# gpr-backplane-schematic-v1.net
KiCad netlist of a schematic drawn in EasyEDA
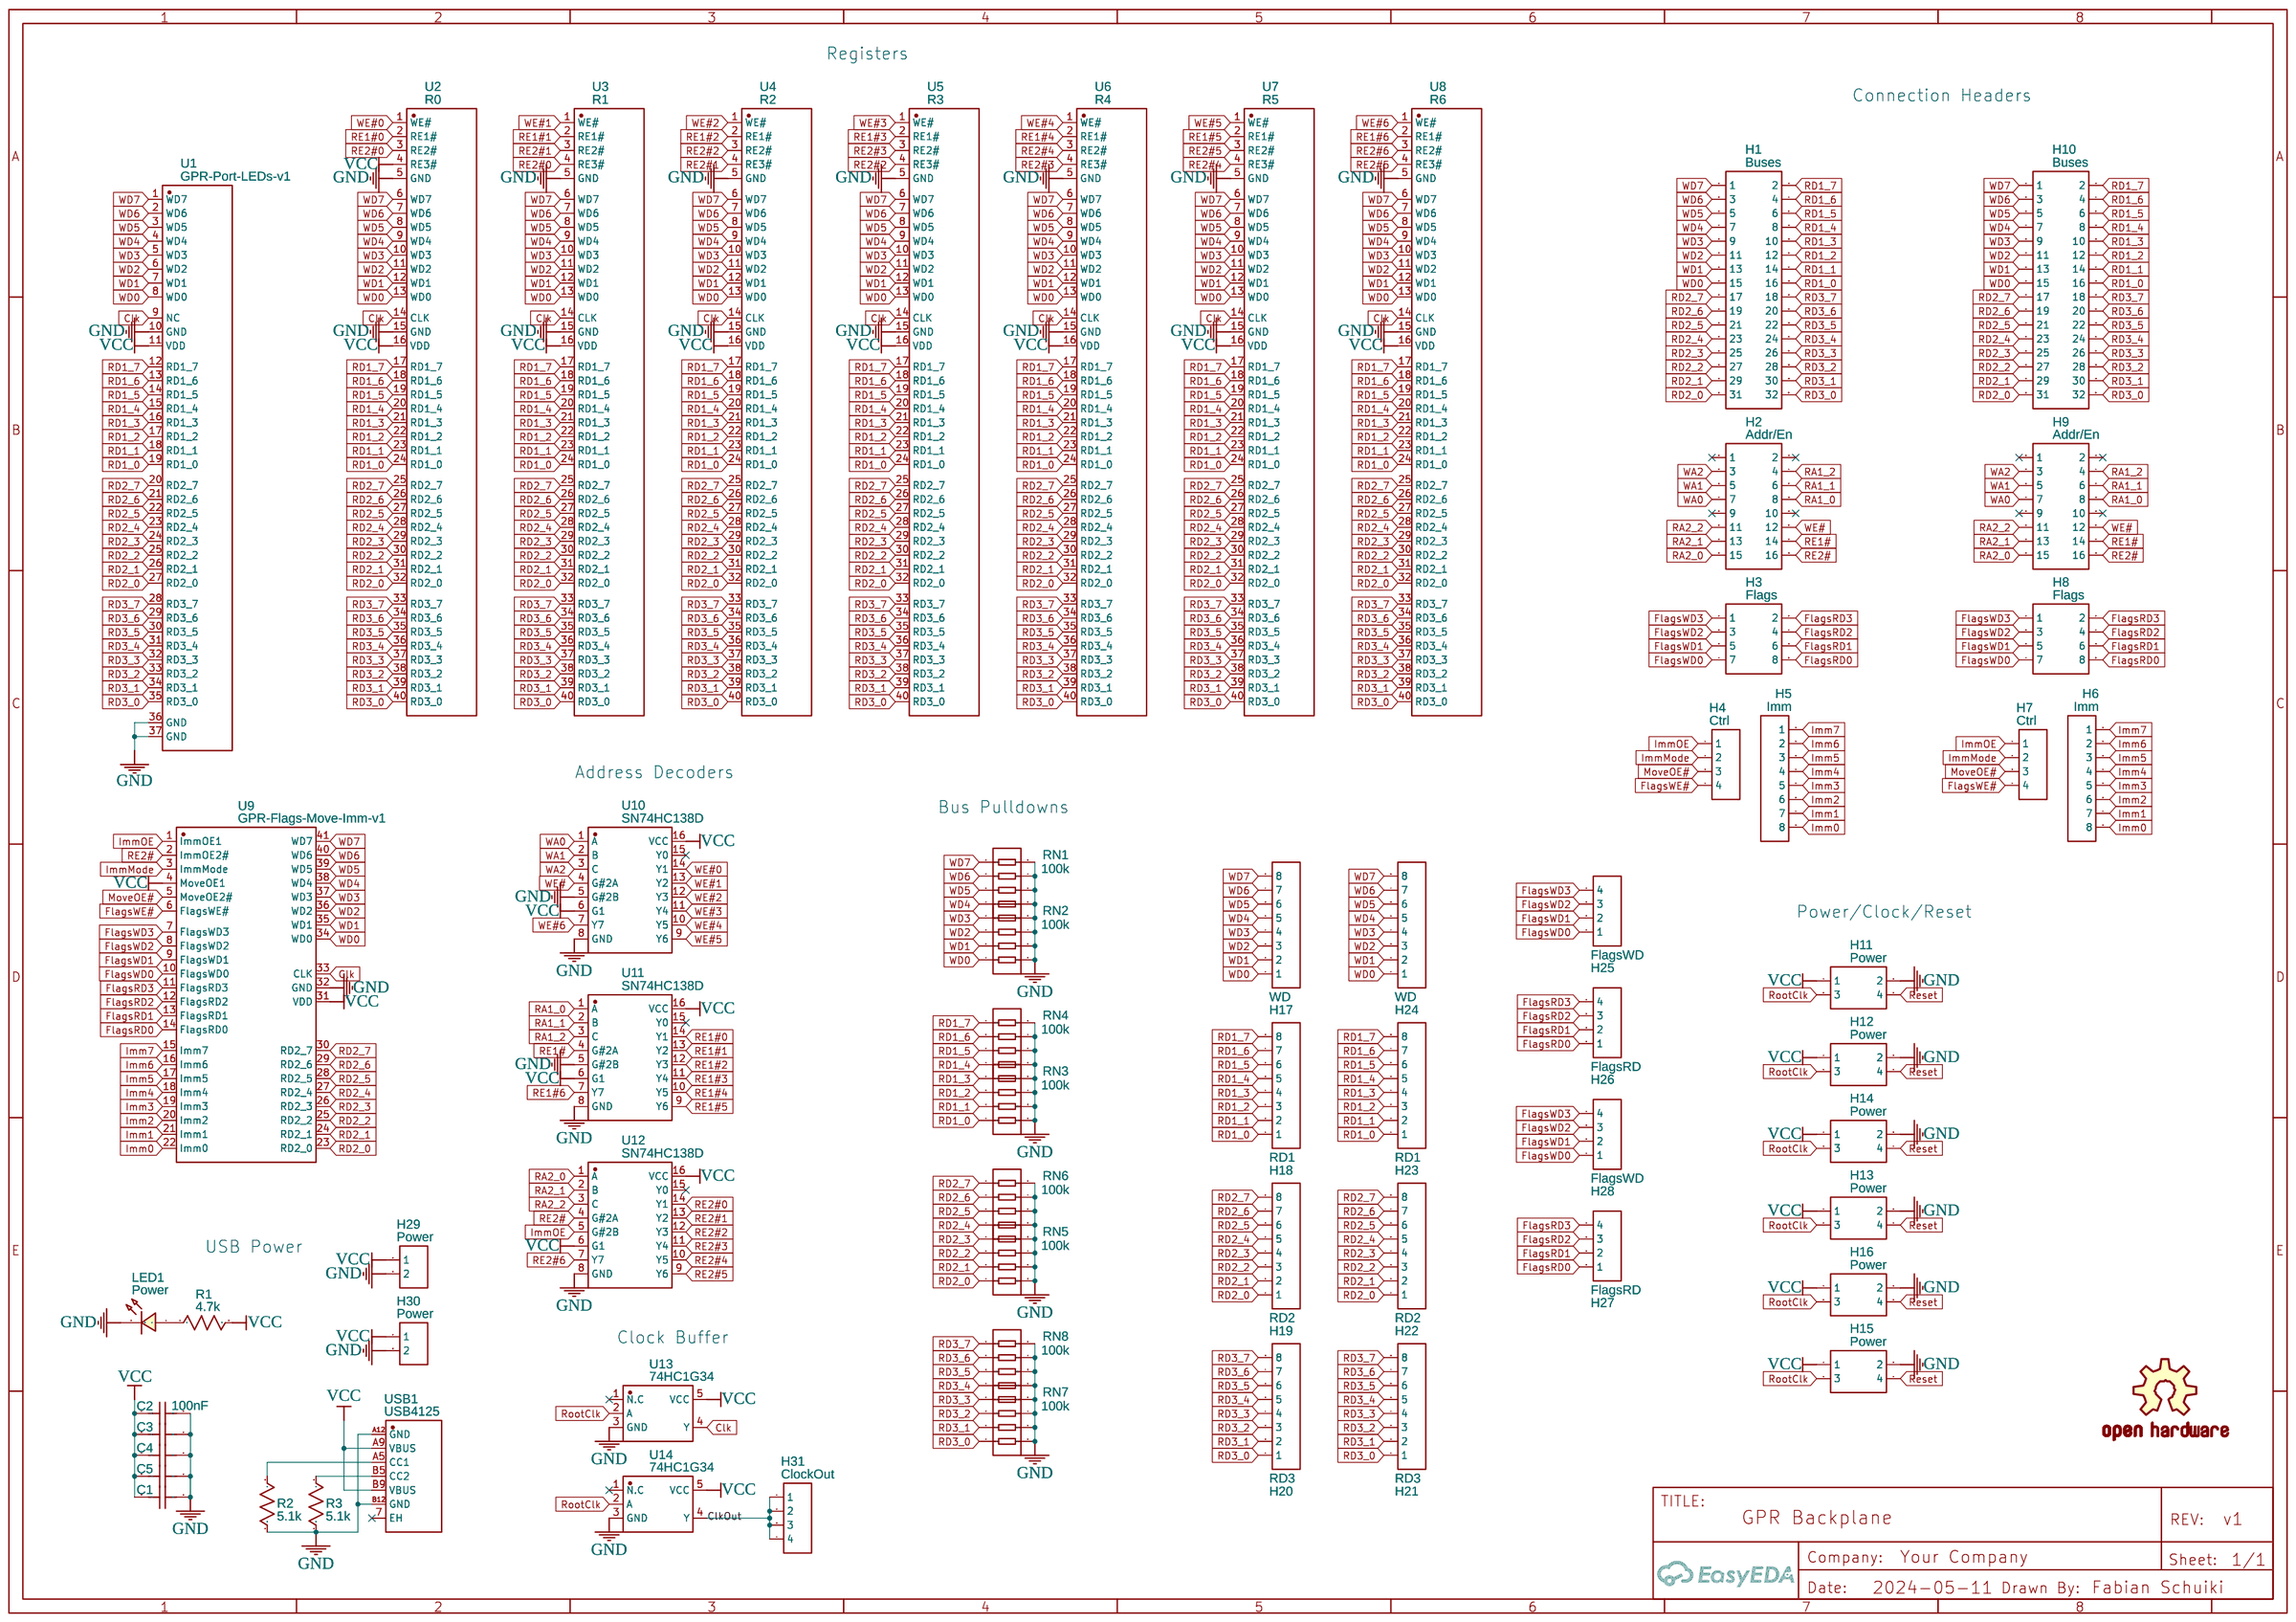
[diagram p0: schematic sheet]

(export (version "E")
  (design (tool "Eeschema 10.0.6"))
  (components
    (comp (ref "C1") (value "100nF") (libsource (lib "") (part "C_0603_US")))
    (comp (ref "C2") (value "100nF") (libsource (lib "") (part "C_0603_US")))
    (comp (ref "C3") (value "100nF") (libsource (lib "") (part "C_0603_US")))
    (comp (ref "C4") (value "100nF") (libsource (lib "") (part "C_0603_US")))
    (comp (ref "C5") (value "100nF") (libsource (lib "") (part "C_0603_US")))
    (comp (ref "H1")
      (value "Buses")
      (fields (field (name "BOM_Supplier Part") "C124382"))
      (libsource (lib "") (part "HDR-F-2.54_2x16"))
    )
    (comp (ref "H2")
      (value "Addr/En")
      (fields (field (name "BOM_Supplier Part") "C30734"))
      (libsource (lib "") (part "HDR-F-2.54_2x8"))
    )
    (comp (ref "H3")
      (value "Flags")
      (fields (field (name "BOM_Supplier Part") "C239344"))
      (libsource (lib "") (part "HDR-F-2.54_2x4"))
    )
    (comp (ref "H4")
      (value "Ctrl")
      (fields (field (name "BOM_Supplier Part") "C225501"))
      (libsource (lib "") (part "HDR-F-2.54_1x4_1"))
    )
    (comp (ref "H5")
      (value "Imm")
      (fields (field (name "BOM_Supplier Part") "C225505"))
      (libsource (lib "") (part "HDR-F-2.54_1x8_1"))
    )
    (comp (ref "H6")
      (value "Imm")
      (fields (field (name "BOM_Supplier Part") "C225505"))
      (libsource (lib "") (part "HDR-F-2.54_1x8_1"))
    )
    (comp (ref "H7")
      (value "Ctrl")
      (fields (field (name "BOM_Supplier Part") "C225501"))
      (libsource (lib "") (part "HDR-F-2.54_1x4_1"))
    )
    (comp (ref "H8")
      (value "Flags")
      (fields (field (name "BOM_Supplier Part") "C239344"))
      (libsource (lib "") (part "HDR-F-2.54_2x4"))
    )
    (comp (ref "H9")
      (value "Addr/En")
      (fields (field (name "BOM_Supplier Part") "C30734"))
      (libsource (lib "") (part "HDR-F-2.54_2x8"))
    )
    (comp (ref "H10")
      (value "Buses")
      (fields (field (name "BOM_Supplier Part") "C124382"))
      (libsource (lib "") (part "HDR-F-2.54_2x16"))
    )
    (comp (ref "H11")
      (value "Power")
      (fields (field (name "BOM_Supplier Part") "C239342"))
      (libsource (lib "") (part "HDR-F-2.54_2x2"))
    )
    (comp (ref "H12")
      (value "Power")
      (fields (field (name "BOM_Supplier Part") "C239342"))
      (libsource (lib "") (part "HDR-F-2.54_2x2"))
    )
    (comp (ref "H13")
      (value "Power")
      (fields (field (name "BOM_Supplier Part") "C239342"))
      (libsource (lib "") (part "HDR-F-2.54_2x2"))
    )
    (comp (ref "H14")
      (value "Power")
      (fields (field (name "BOM_Supplier Part") "C239342"))
      (libsource (lib "") (part "HDR-F-2.54_2x2"))
    )
    (comp (ref "H15")
      (value "Power")
      (fields (field (name "BOM_Supplier Part") "C239342"))
      (libsource (lib "") (part "HDR-F-2.54_2x2"))
    )
    (comp (ref "H16")
      (value "Power")
      (fields (field (name "BOM_Supplier Part") "C239342"))
      (libsource (lib "") (part "HDR-F-2.54_2x2"))
    )
    (comp (ref "H17")
      (value "WD")
      (fields (field (name "BOM_Supplier Part") "C225505"))
      (libsource (lib "") (part "HDR-F-2.54_1x8"))
    )
    (comp (ref "H18")
      (value "RD1")
      (fields (field (name "BOM_Supplier Part") "C225505"))
      (libsource (lib "") (part "HDR-F-2.54_1x8"))
    )
    (comp (ref "H19")
      (value "RD2")
      (fields (field (name "BOM_Supplier Part") "C225505"))
      (libsource (lib "") (part "HDR-F-2.54_1x8"))
    )
    (comp (ref "H20")
      (value "RD3")
      (fields (field (name "BOM_Supplier Part") "C225505"))
      (libsource (lib "") (part "HDR-F-2.54_1x8"))
    )
    (comp (ref "H21")
      (value "RD3")
      (fields (field (name "BOM_Supplier Part") "C225505"))
      (libsource (lib "") (part "HDR-F-2.54_1x8"))
    )
    (comp (ref "H22")
      (value "RD2")
      (fields (field (name "BOM_Supplier Part") "C225505"))
      (libsource (lib "") (part "HDR-F-2.54_1x8"))
    )
    (comp (ref "H23")
      (value "RD1")
      (fields (field (name "BOM_Supplier Part") "C225505"))
      (libsource (lib "") (part "HDR-F-2.54_1x8"))
    )
    (comp (ref "H24")
      (value "WD")
      (fields (field (name "BOM_Supplier Part") "C225505"))
      (libsource (lib "") (part "HDR-F-2.54_1x8"))
    )
    (comp (ref "H25")
      (value "FlagsWD")
      (fields (field (name "BOM_Supplier Part") "C225501"))
      (libsource (lib "") (part "HDR-F-2.54_1x4"))
    )
    (comp (ref "H26")
      (value "FlagsRD")
      (fields (field (name "BOM_Supplier Part") "C225501"))
      (libsource (lib "") (part "HDR-F-2.54_1x4"))
    )
    (comp (ref "H27")
      (value "FlagsRD")
      (fields (field (name "BOM_Supplier Part") "C225501"))
      (libsource (lib "") (part "HDR-F-2.54_1x4"))
    )
    (comp (ref "H28")
      (value "FlagsWD")
      (fields (field (name "BOM_Supplier Part") "C225501"))
      (libsource (lib "") (part "HDR-F-2.54_1x4"))
    )
    (comp (ref "H29")
      (value "Power")
      (fields (field (name "BOM_Supplier Part") "C49661"))
      (libsource (lib "") (part "HDR-F-2.54_1x2"))
    )
    (comp (ref "H30")
      (value "Power")
      (fields (field (name "BOM_Supplier Part") "C49661"))
      (libsource (lib "") (part "HDR-F-2.54_1x2"))
    )
    (comp (ref "H31")
      (value "ClockOut")
      (fields (field (name "BOM_Supplier Part") "C225501"))
      (libsource (lib "") (part "HDR-F-2.54_1x4_1"))
    )
    (comp (ref "LED1")
      (value "Power")
      (fields
        (field (name "BOM_Manufacturer Part") "D-B080508B1-KS2")
        (field (name "BOM_Supplier Part") "C108412")
      )
      (libsource (lib "") (part "LED-0805_B"))
    )
    (comp (ref "LOGO1") (value "ChannelLogo") (libsource (lib "") (part "ChannelLogo")))
    (comp (ref "LOGO2") (value "OSHW-LOGOL") (libsource (lib "") (part "OSHW-LOGOL")))
    (comp (ref "R1") (value "4.7k") (libsource (lib "") (part "R_0603_US_1")))
    (comp (ref "R2") (value "5.1k") (libsource (lib "") (part "R_0603_US")))
    (comp (ref "R3") (value "5.1k") (libsource (lib "") (part "R_0603_US")))
    (comp (ref "RN1")
      (value "100k")
      (fields
        (field (name "BOM_Manufacturer Part") "4D03WGJ0753T5E")
        (field (name "BOM_Supplier Part") "C425056")
      )
      (libsource (lib "") (part "4D03WGJ0753T5E"))
    )
    (comp (ref "RN2")
      (value "100k")
      (fields
        (field (name "BOM_Manufacturer Part") "4D03WGJ0753T5E")
        (field (name "BOM_Supplier Part") "C425056")
      )
      (libsource (lib "") (part "4D03WGJ0753T5E"))
    )
    (comp (ref "RN3")
      (value "100k")
      (fields
        (field (name "BOM_Manufacturer Part") "4D03WGJ0753T5E")
        (field (name "BOM_Supplier Part") "C425056")
      )
      (libsource (lib "") (part "4D03WGJ0753T5E"))
    )
    (comp (ref "RN4")
      (value "100k")
      (fields
        (field (name "BOM_Manufacturer Part") "4D03WGJ0753T5E")
        (field (name "BOM_Supplier Part") "C425056")
      )
      (libsource (lib "") (part "4D03WGJ0753T5E"))
    )
    (comp (ref "RN5")
      (value "100k")
      (fields
        (field (name "BOM_Manufacturer Part") "4D03WGJ0753T5E")
        (field (name "BOM_Supplier Part") "C425056")
      )
      (libsource (lib "") (part "4D03WGJ0753T5E"))
    )
    (comp (ref "RN6")
      (value "100k")
      (fields
        (field (name "BOM_Manufacturer Part") "4D03WGJ0753T5E")
        (field (name "BOM_Supplier Part") "C425056")
      )
      (libsource (lib "") (part "4D03WGJ0753T5E"))
    )
    (comp (ref "RN7")
      (value "100k")
      (fields
        (field (name "BOM_Manufacturer Part") "4D03WGJ0753T5E")
        (field (name "BOM_Supplier Part") "C425056")
      )
      (libsource (lib "") (part "4D03WGJ0753T5E"))
    )
    (comp (ref "RN8")
      (value "100k")
      (fields
        (field (name "BOM_Manufacturer Part") "4D03WGJ0753T5E")
        (field (name "BOM_Supplier Part") "C425056")
      )
      (libsource (lib "") (part "4D03WGJ0753T5E"))
    )
    (comp (ref "U1") (value "GPR-Port-LEDs-v1") (libsource (lib "") (part "GPR-Port-LEDs-v1")))
    (comp (ref "U2") (value "R0") (libsource (lib "") (part "GPR-v1")))
    (comp (ref "U3") (value "R1") (libsource (lib "") (part "GPR-v1")))
    (comp (ref "U4") (value "R2") (libsource (lib "") (part "GPR-v1")))
    (comp (ref "U5") (value "R3") (libsource (lib "") (part "GPR-v1")))
    (comp (ref "U6") (value "R4") (libsource (lib "") (part "GPR-v1")))
    (comp (ref "U7") (value "R5") (libsource (lib "") (part "GPR-v1")))
    (comp (ref "U8") (value "R6") (libsource (lib "") (part "GPR-v1")))
    (comp (ref "U9") (value "GPR-Flags-Move-Imm-v1") (libsource (lib "") (part "GPR-Flags-Move-Imm-v1")))
    (comp (ref "U10")
      (value "SN74HC138D")
      (fields (field (name "Manufacturer") "TI(德州仪器)"))
      (libsource (lib "") (part "SN74HC138D"))
    )
    (comp (ref "U11")
      (value "SN74HC138D")
      (fields (field (name "Manufacturer") "TI(德州仪器)"))
      (libsource (lib "") (part "SN74HC138D"))
    )
    (comp (ref "U12")
      (value "SN74HC138D")
      (fields (field (name "Manufacturer") "TI(德州仪器)"))
      (libsource (lib "") (part "SN74HC138D"))
    )
    (comp (ref "U13")
      (value "74HC1G34")
      (fields (field (name "Manufacturer Part") "SN74LVC1G34DBVRG4") (field (name "Manufacturer") "TI(德州仪器)"))
      (libsource (lib "") (part "SN74LVC1G34DBVRG4"))
    )
    (comp (ref "U14")
      (value "74HC1G34")
      (fields (field (name "Manufacturer Part") "SN74LVC1G34DBVRG4") (field (name "Manufacturer") "TI(德州仪器)"))
      (libsource (lib "") (part "SN74LVC1G34DBVRG4"))
    )
    (comp (ref "USB1")
      (value "USB4125")
      (fields
        (field (name "Manufacturer Part") "00401-UCAF001-X")
        (field (name "Manufacturer") "MINTRON(明硕)")
      )
      (libsource (lib "") (part "00401-UCAF001-X"))
    )
  )
  (nets
    (net (code "1") (name "/ClkOut") (class "Default")
      (node (ref "H31") (pin "1") (pinfunction "1_1") (pintype "unspecified"))
      (node (ref "H31") (pin "2") (pinfunction "2_2") (pintype "unspecified"))
      (node (ref "H31") (pin "3") (pinfunction "3_3") (pintype "unspecified"))
      (node (ref "H31") (pin "4") (pinfunction "4_4") (pintype "unspecified"))
      (node (ref "U14") (pin "4") (pinfunction "Y_4") (pintype "unspecified"))
    )
    (net (code "2") (name "Clk") (class "Default")
      (node (ref "U1") (pin "9") (pinfunction "NC_9") (pintype "unspecified"))
      (node (ref "U13") (pin "4") (pinfunction "Y_4") (pintype "unspecified"))
      (node (ref "U2") (pin "14") (pinfunction "CLK_14") (pintype "unspecified"))
      (node (ref "U3") (pin "14") (pinfunction "CLK_14") (pintype "unspecified"))
      (node (ref "U4") (pin "14") (pinfunction "CLK_14") (pintype "unspecified"))
      (node (ref "U5") (pin "14") (pinfunction "CLK_14") (pintype "unspecified"))
      (node (ref "U6") (pin "14") (pinfunction "CLK_14") (pintype "unspecified"))
      (node (ref "U7") (pin "14") (pinfunction "CLK_14") (pintype "unspecified"))
      (node (ref "U8") (pin "14") (pinfunction "CLK_14") (pintype "unspecified"))
      (node (ref "U9") (pin "33") (pinfunction "CLK_33") (pintype "unspecified"))
    )
    (net (code "3") (name "FlagsRD0") (class "Default")
      (node (ref "H26") (pin "1") (pinfunction "1_1") (pintype "unspecified"))
      (node (ref "H27") (pin "1") (pinfunction "1_1") (pintype "unspecified"))
      (node (ref "H3") (pin "8") (pinfunction "8_8") (pintype "unspecified"))
      (node (ref "H8") (pin "8") (pinfunction "8_8") (pintype "unspecified"))
      (node (ref "U9") (pin "14") (pinfunction "FlagsRD0_14") (pintype "unspecified"))
    )
    (net (code "4") (name "FlagsRD1") (class "Default")
      (node (ref "H26") (pin "2") (pinfunction "2_2") (pintype "unspecified"))
      (node (ref "H27") (pin "2") (pinfunction "2_2") (pintype "unspecified"))
      (node (ref "H3") (pin "6") (pinfunction "6_6") (pintype "unspecified"))
      (node (ref "H8") (pin "6") (pinfunction "6_6") (pintype "unspecified"))
      (node (ref "U9") (pin "13") (pinfunction "FlagsRD1_13") (pintype "unspecified"))
    )
    (net (code "5") (name "FlagsRD2") (class "Default")
      (node (ref "H26") (pin "3") (pinfunction "3_3") (pintype "unspecified"))
      (node (ref "H27") (pin "3") (pinfunction "3_3") (pintype "unspecified"))
      (node (ref "H3") (pin "4") (pinfunction "4_4") (pintype "unspecified"))
      (node (ref "H8") (pin "4") (pinfunction "4_4") (pintype "unspecified"))
      (node (ref "U9") (pin "12") (pinfunction "FlagsRD2_12") (pintype "unspecified"))
    )
    (net (code "6") (name "FlagsRD3") (class "Default")
      (node (ref "H26") (pin "4") (pinfunction "4_4") (pintype "unspecified"))
      (node (ref "H27") (pin "4") (pinfunction "4_4") (pintype "unspecified"))
      (node (ref "H3") (pin "2") (pinfunction "2_2") (pintype "unspecified"))
      (node (ref "H8") (pin "2") (pinfunction "2_2") (pintype "unspecified"))
      (node (ref "U9") (pin "11") (pinfunction "FlagsRD3_11") (pintype "unspecified"))
    )
    (net (code "7") (name "FlagsWD0") (class "Default")
      (node (ref "H25") (pin "1") (pinfunction "1_1") (pintype "unspecified"))
      (node (ref "H28") (pin "1") (pinfunction "1_1") (pintype "unspecified"))
      (node (ref "H3") (pin "7") (pinfunction "7_7") (pintype "unspecified"))
      (node (ref "H8") (pin "7") (pinfunction "7_7") (pintype "unspecified"))
      (node (ref "U9") (pin "10") (pinfunction "FlagsWD0_10") (pintype "unspecified"))
    )
    (net (code "8") (name "FlagsWD1") (class "Default")
      (node (ref "H25") (pin "2") (pinfunction "2_2") (pintype "unspecified"))
      (node (ref "H28") (pin "2") (pinfunction "2_2") (pintype "unspecified"))
      (node (ref "H3") (pin "5") (pinfunction "5_5") (pintype "unspecified"))
      (node (ref "H8") (pin "5") (pinfunction "5_5") (pintype "unspecified"))
      (node (ref "U9") (pin "9") (pinfunction "FlagsWD1_9") (pintype "unspecified"))
    )
    (net (code "9") (name "FlagsWD2") (class "Default")
      (node (ref "H25") (pin "3") (pinfunction "3_3") (pintype "unspecified"))
      (node (ref "H28") (pin "3") (pinfunction "3_3") (pintype "unspecified"))
      (node (ref "H3") (pin "3") (pinfunction "3_3") (pintype "unspecified"))
      (node (ref "H8") (pin "3") (pinfunction "3_3") (pintype "unspecified"))
      (node (ref "U9") (pin "8") (pinfunction "FlagsWD2_8") (pintype "unspecified"))
    )
    (net (code "10") (name "FlagsWD3") (class "Default")
      (node (ref "H25") (pin "4") (pinfunction "4_4") (pintype "unspecified"))
      (node (ref "H28") (pin "4") (pinfunction "4_4") (pintype "unspecified"))
      (node (ref "H3") (pin "1") (pinfunction "1_1") (pintype "unspecified"))
      (node (ref "H8") (pin "1") (pinfunction "1_1") (pintype "unspecified"))
      (node (ref "U9") (pin "7") (pinfunction "FlagsWD3_7") (pintype "unspecified"))
    )
    (net (code "11") (name "FlagsWE#") (class "Default")
      (node (ref "H4") (pin "4") (pinfunction "4_4") (pintype "unspecified"))
      (node (ref "H7") (pin "4") (pinfunction "4_4") (pintype "unspecified"))
      (node (ref "U9") (pin "6") (pinfunction "FlagsWE#_6") (pintype "unspecified"))
    )
    (net (code "12") (name "GND") (class "Default")
      (node (ref "C1") (pin "2") (pinfunction "2_2") (pintype "unspecified"))
      (node (ref "C2") (pin "2") (pinfunction "2_2") (pintype "unspecified"))
      (node (ref "C3") (pin "2") (pinfunction "2_2") (pintype "unspecified"))
      (node (ref "C4") (pin "2") (pinfunction "2_2") (pintype "unspecified"))
      (node (ref "C5") (pin "2") (pinfunction "2_2") (pintype "unspecified"))
      (node (ref "H11") (pin "2") (pinfunction "2_2") (pintype "unspecified"))
      (node (ref "H12") (pin "2") (pinfunction "2_2") (pintype "unspecified"))
      (node (ref "H13") (pin "2") (pinfunction "2_2") (pintype "unspecified"))
      (node (ref "H14") (pin "2") (pinfunction "2_2") (pintype "unspecified"))
      (node (ref "H15") (pin "2") (pinfunction "2_2") (pintype "unspecified"))
      (node (ref "H16") (pin "2") (pinfunction "2_2") (pintype "unspecified"))
      (node (ref "H29") (pin "2") (pinfunction "2_2") (pintype "input"))
      (node (ref "H30") (pin "2") (pinfunction "2_2") (pintype "input"))
      (node (ref "LED1") (pin "2") (pinfunction "2_2") (pintype "unspecified"))
      (node (ref "R2") (pin "1") (pinfunction "1_1") (pintype "unspecified"))
      (node (ref "R3") (pin "1") (pinfunction "1_1") (pintype "unspecified"))
      (node (ref "RN1") (pin "5") (pinfunction "5_5") (pintype "unspecified"))
      (node (ref "RN1") (pin "6") (pinfunction "6_6") (pintype "unspecified"))
      (node (ref "RN1") (pin "7") (pinfunction "7_7") (pintype "unspecified"))
      (node (ref "RN1") (pin "8") (pinfunction "8_8") (pintype "unspecified"))
      (node (ref "RN2") (pin "5") (pinfunction "5_5") (pintype "unspecified"))
      (node (ref "RN2") (pin "6") (pinfunction "6_6") (pintype "unspecified"))
      (node (ref "RN2") (pin "7") (pinfunction "7_7") (pintype "unspecified"))
      (node (ref "RN2") (pin "8") (pinfunction "8_8") (pintype "unspecified"))
      (node (ref "RN3") (pin "5") (pinfunction "5_5") (pintype "unspecified"))
      (node (ref "RN3") (pin "6") (pinfunction "6_6") (pintype "unspecified"))
      (node (ref "RN3") (pin "7") (pinfunction "7_7") (pintype "unspecified"))
      (node (ref "RN3") (pin "8") (pinfunction "8_8") (pintype "unspecified"))
      (node (ref "RN4") (pin "5") (pinfunction "5_5") (pintype "unspecified"))
      (node (ref "RN4") (pin "6") (pinfunction "6_6") (pintype "unspecified"))
      (node (ref "RN4") (pin "7") (pinfunction "7_7") (pintype "unspecified"))
      (node (ref "RN4") (pin "8") (pinfunction "8_8") (pintype "unspecified"))
      (node (ref "RN5") (pin "5") (pinfunction "5_5") (pintype "unspecified"))
      (node (ref "RN5") (pin "6") (pinfunction "6_6") (pintype "unspecified"))
      (node (ref "RN5") (pin "7") (pinfunction "7_7") (pintype "unspecified"))
      (node (ref "RN5") (pin "8") (pinfunction "8_8") (pintype "unspecified"))
      (node (ref "RN6") (pin "5") (pinfunction "5_5") (pintype "unspecified"))
      (node (ref "RN6") (pin "6") (pinfunction "6_6") (pintype "unspecified"))
      (node (ref "RN6") (pin "7") (pinfunction "7_7") (pintype "unspecified"))
      (node (ref "RN6") (pin "8") (pinfunction "8_8") (pintype "unspecified"))
      (node (ref "RN7") (pin "5") (pinfunction "5_5") (pintype "unspecified"))
      (node (ref "RN7") (pin "6") (pinfunction "6_6") (pintype "unspecified"))
      (node (ref "RN7") (pin "7") (pinfunction "7_7") (pintype "unspecified"))
      (node (ref "RN7") (pin "8") (pinfunction "8_8") (pintype "unspecified"))
      (node (ref "RN8") (pin "5") (pinfunction "5_5") (pintype "unspecified"))
      (node (ref "RN8") (pin "6") (pinfunction "6_6") (pintype "unspecified"))
      (node (ref "RN8") (pin "7") (pinfunction "7_7") (pintype "unspecified"))
      (node (ref "RN8") (pin "8") (pinfunction "8_8") (pintype "unspecified"))
      (node (ref "U1") (pin "10") (pinfunction "GND_10") (pintype "unspecified"))
      (node (ref "U1") (pin "36") (pinfunction "GND_36") (pintype "unspecified"))
      (node (ref "U1") (pin "37") (pinfunction "GND_37") (pintype "unspecified"))
      (node (ref "U10") (pin "5") (pinfunction "G#2B_5") (pintype "unspecified"))
      (node (ref "U10") (pin "8") (pinfunction "GND_8") (pintype "unspecified"))
      (node (ref "U11") (pin "5") (pinfunction "G#2B_5") (pintype "unspecified"))
      (node (ref "U11") (pin "8") (pinfunction "GND_8") (pintype "unspecified"))
      (node (ref "U12") (pin "8") (pinfunction "GND_8") (pintype "unspecified"))
      (node (ref "U13") (pin "3") (pinfunction "GND_3") (pintype "unspecified"))
      (node (ref "U14") (pin "3") (pinfunction "GND_3") (pintype "unspecified"))
      (node (ref "U2") (pin "15") (pinfunction "GND_15") (pintype "unspecified"))
      (node (ref "U2") (pin "5") (pinfunction "GND_5") (pintype "unspecified"))
      (node (ref "U3") (pin "15") (pinfunction "GND_15") (pintype "unspecified"))
      (node (ref "U3") (pin "5") (pinfunction "GND_5") (pintype "unspecified"))
      (node (ref "U4") (pin "15") (pinfunction "GND_15") (pintype "unspecified"))
      (node (ref "U4") (pin "5") (pinfunction "GND_5") (pintype "unspecified"))
      (node (ref "U5") (pin "15") (pinfunction "GND_15") (pintype "unspecified"))
      (node (ref "U5") (pin "5") (pinfunction "GND_5") (pintype "unspecified"))
      (node (ref "U6") (pin "15") (pinfunction "GND_15") (pintype "unspecified"))
      (node (ref "U6") (pin "5") (pinfunction "GND_5") (pintype "unspecified"))
      (node (ref "U7") (pin "15") (pinfunction "GND_15") (pintype "unspecified"))
      (node (ref "U7") (pin "5") (pinfunction "GND_5") (pintype "unspecified"))
      (node (ref "U8") (pin "15") (pinfunction "GND_15") (pintype "unspecified"))
      (node (ref "U8") (pin "5") (pinfunction "GND_5") (pintype "unspecified"))
      (node (ref "U9") (pin "32") (pinfunction "GND_32") (pintype "unspecified"))
      (node (ref "USB1") (pin "A12") (pinfunction "GND_A12") (pintype "unspecified"))
      (node (ref "USB1") (pin "B12") (pinfunction "GND_B12") (pintype "unspecified"))
    )
    (net (code "13") (name "Imm0") (class "Default")
      (node (ref "H5") (pin "8") (pinfunction "8_8") (pintype "unspecified"))
      (node (ref "H6") (pin "8") (pinfunction "8_8") (pintype "unspecified"))
      (node (ref "U9") (pin "22") (pinfunction "Imm0_22") (pintype "unspecified"))
    )
    (net (code "14") (name "Imm1") (class "Default")
      (node (ref "H5") (pin "7") (pinfunction "7_7") (pintype "unspecified"))
      (node (ref "H6") (pin "7") (pinfunction "7_7") (pintype "unspecified"))
      (node (ref "U9") (pin "21") (pinfunction "Imm1_21") (pintype "unspecified"))
    )
    (net (code "15") (name "Imm2") (class "Default")
      (node (ref "H5") (pin "6") (pinfunction "6_6") (pintype "unspecified"))
      (node (ref "H6") (pin "6") (pinfunction "6_6") (pintype "unspecified"))
      (node (ref "U9") (pin "20") (pinfunction "Imm2_20") (pintype "unspecified"))
    )
    (net (code "16") (name "Imm3") (class "Default")
      (node (ref "H5") (pin "5") (pinfunction "5_5") (pintype "unspecified"))
      (node (ref "H6") (pin "5") (pinfunction "5_5") (pintype "unspecified"))
      (node (ref "U9") (pin "19") (pinfunction "Imm3_19") (pintype "unspecified"))
    )
    (net (code "17") (name "Imm4") (class "Default")
      (node (ref "H5") (pin "4") (pinfunction "4_4") (pintype "unspecified"))
      (node (ref "H6") (pin "4") (pinfunction "4_4") (pintype "unspecified"))
      (node (ref "U9") (pin "18") (pinfunction "Imm4_18") (pintype "unspecified"))
    )
    (net (code "18") (name "Imm5") (class "Default")
      (node (ref "H5") (pin "3") (pinfunction "3_3") (pintype "unspecified"))
      (node (ref "H6") (pin "3") (pinfunction "3_3") (pintype "unspecified"))
      (node (ref "U9") (pin "17") (pinfunction "Imm5_17") (pintype "unspecified"))
    )
    (net (code "19") (name "Imm6") (class "Default")
      (node (ref "H5") (pin "2") (pinfunction "2_2") (pintype "unspecified"))
      (node (ref "H6") (pin "2") (pinfunction "2_2") (pintype "unspecified"))
      (node (ref "U9") (pin "16") (pinfunction "Imm6_16") (pintype "unspecified"))
    )
    (net (code "20") (name "Imm7") (class "Default")
      (node (ref "H5") (pin "1") (pinfunction "1_1") (pintype "unspecified"))
      (node (ref "H6") (pin "1") (pinfunction "1_1") (pintype "unspecified"))
      (node (ref "U9") (pin "15") (pinfunction "Imm7_15") (pintype "unspecified"))
    )
    (net (code "21") (name "ImmMode") (class "Default")
      (node (ref "H4") (pin "2") (pinfunction "2_2") (pintype "unspecified"))
      (node (ref "H7") (pin "2") (pinfunction "2_2") (pintype "unspecified"))
      (node (ref "U9") (pin "3") (pinfunction "ImmMode_3") (pintype "unspecified"))
    )
    (net (code "22") (name "ImmOE") (class "Default")
      (node (ref "H4") (pin "1") (pinfunction "1_1") (pintype "unspecified"))
      (node (ref "H7") (pin "1") (pinfunction "1_1") (pintype "unspecified"))
      (node (ref "U12") (pin "5") (pinfunction "G#2B_5") (pintype "unspecified"))
      (node (ref "U9") (pin "1") (pinfunction "ImmOE1_1") (pintype "unspecified"))
    )
    (net (code "23") (name "MoveOE#") (class "Default")
      (node (ref "H4") (pin "3") (pinfunction "3_3") (pintype "unspecified"))
      (node (ref "H7") (pin "3") (pinfunction "3_3") (pintype "unspecified"))
      (node (ref "U9") (pin "5") (pinfunction "MoveOE2#_5") (pintype "unspecified"))
    )
    (net (code "24") (name "Net-(LED1-Pad1)") (class "Default")
      (node (ref "LED1") (pin "1") (pinfunction "1_1") (pintype "unspecified"))
      (node (ref "R1") (pin "1") (pinfunction "1_1") (pintype "unspecified"))
    )
    (net (code "25") (name "Net-(USB1-CC1)") (class "Default")
      (node (ref "R2") (pin "2") (pinfunction "2_2") (pintype "unspecified"))
      (node (ref "USB1") (pin "A5") (pinfunction "CC1_A5") (pintype "unspecified"))
    )
    (net (code "26") (name "Net-(USB1-CC2)") (class "Default")
      (node (ref "R3") (pin "2") (pinfunction "2_2") (pintype "unspecified"))
      (node (ref "USB1") (pin "B5") (pinfunction "CC2_B5") (pintype "unspecified"))
    )
    (net (code "27") (name "RA1_0") (class "Default")
      (node (ref "H2") (pin "8") (pinfunction "8_8") (pintype "input"))
      (node (ref "H9") (pin "8") (pinfunction "8_8") (pintype "input"))
      (node (ref "U11") (pin "1") (pinfunction "A_1") (pintype "unspecified"))
    )
    (net (code "28") (name "RA1_1") (class "Default")
      (node (ref "H2") (pin "6") (pinfunction "6_6") (pintype "input"))
      (node (ref "H9") (pin "6") (pinfunction "6_6") (pintype "input"))
      (node (ref "U11") (pin "2") (pinfunction "B_2") (pintype "unspecified"))
    )
    (net (code "29") (name "RA1_2") (class "Default")
      (node (ref "H2") (pin "4") (pinfunction "4_4") (pintype "input"))
      (node (ref "H9") (pin "4") (pinfunction "4_4") (pintype "input"))
      (node (ref "U11") (pin "3") (pinfunction "C_3") (pintype "unspecified"))
    )
    (net (code "30") (name "RA2_0") (class "Default")
      (node (ref "H2") (pin "15") (pinfunction "15_15") (pintype "input"))
      (node (ref "H9") (pin "15") (pinfunction "15_15") (pintype "input"))
      (node (ref "U12") (pin "1") (pinfunction "A_1") (pintype "unspecified"))
    )
    (net (code "31") (name "RA2_1") (class "Default")
      (node (ref "H2") (pin "13") (pinfunction "13_13") (pintype "input"))
      (node (ref "H9") (pin "13") (pinfunction "13_13") (pintype "input"))
      (node (ref "U12") (pin "2") (pinfunction "B_2") (pintype "unspecified"))
    )
    (net (code "32") (name "RA2_2") (class "Default")
      (node (ref "H2") (pin "11") (pinfunction "11_11") (pintype "input"))
      (node (ref "H9") (pin "11") (pinfunction "11_11") (pintype "input"))
      (node (ref "U12") (pin "3") (pinfunction "C_3") (pintype "unspecified"))
    )
    (net (code "33") (name "RD1_0") (class "Default")
      (node (ref "H1") (pin "16") (pinfunction "16_16") (pintype "input"))
      (node (ref "H10") (pin "16") (pinfunction "16_16") (pintype "input"))
      (node (ref "H18") (pin "1") (pinfunction "1_1") (pintype "unspecified"))
      (node (ref "H23") (pin "1") (pinfunction "1_1") (pintype "unspecified"))
      (node (ref "RN3") (pin "4") (pinfunction "4_4") (pintype "unspecified"))
      (node (ref "U1") (pin "19") (pinfunction "RD1_0_19") (pintype "unspecified"))
      (node (ref "U2") (pin "24") (pinfunction "RD1_0_24") (pintype "unspecified"))
      (node (ref "U3") (pin "24") (pinfunction "RD1_0_24") (pintype "unspecified"))
      (node (ref "U4") (pin "24") (pinfunction "RD1_0_24") (pintype "unspecified"))
      (node (ref "U5") (pin "24") (pinfunction "RD1_0_24") (pintype "unspecified"))
      (node (ref "U6") (pin "24") (pinfunction "RD1_0_24") (pintype "unspecified"))
      (node (ref "U7") (pin "24") (pinfunction "RD1_0_24") (pintype "unspecified"))
      (node (ref "U8") (pin "24") (pinfunction "RD1_0_24") (pintype "unspecified"))
    )
    (net (code "34") (name "RD1_1") (class "Default")
      (node (ref "H1") (pin "14") (pinfunction "14_14") (pintype "input"))
      (node (ref "H10") (pin "14") (pinfunction "14_14") (pintype "input"))
      (node (ref "H18") (pin "2") (pinfunction "2_2") (pintype "unspecified"))
      (node (ref "H23") (pin "2") (pinfunction "2_2") (pintype "unspecified"))
      (node (ref "RN3") (pin "3") (pinfunction "3_3") (pintype "unspecified"))
      (node (ref "U1") (pin "18") (pinfunction "RD1_1_18") (pintype "unspecified"))
      (node (ref "U2") (pin "23") (pinfunction "RD1_1_23") (pintype "unspecified"))
      (node (ref "U3") (pin "23") (pinfunction "RD1_1_23") (pintype "unspecified"))
      (node (ref "U4") (pin "23") (pinfunction "RD1_1_23") (pintype "unspecified"))
      (node (ref "U5") (pin "23") (pinfunction "RD1_1_23") (pintype "unspecified"))
      (node (ref "U6") (pin "23") (pinfunction "RD1_1_23") (pintype "unspecified"))
      (node (ref "U7") (pin "23") (pinfunction "RD1_1_23") (pintype "unspecified"))
      (node (ref "U8") (pin "23") (pinfunction "RD1_1_23") (pintype "unspecified"))
    )
    (net (code "35") (name "RD1_2") (class "Default")
      (node (ref "H1") (pin "12") (pinfunction "12_12") (pintype "input"))
      (node (ref "H10") (pin "12") (pinfunction "12_12") (pintype "input"))
      (node (ref "H18") (pin "3") (pinfunction "3_3") (pintype "unspecified"))
      (node (ref "H23") (pin "3") (pinfunction "3_3") (pintype "unspecified"))
      (node (ref "RN3") (pin "2") (pinfunction "2_2") (pintype "unspecified"))
      (node (ref "U1") (pin "17") (pinfunction "RD1_2_17") (pintype "unspecified"))
      (node (ref "U2") (pin "22") (pinfunction "RD1_2_22") (pintype "unspecified"))
      (node (ref "U3") (pin "22") (pinfunction "RD1_2_22") (pintype "unspecified"))
      (node (ref "U4") (pin "22") (pinfunction "RD1_2_22") (pintype "unspecified"))
      (node (ref "U5") (pin "22") (pinfunction "RD1_2_22") (pintype "unspecified"))
      (node (ref "U6") (pin "22") (pinfunction "RD1_2_22") (pintype "unspecified"))
      (node (ref "U7") (pin "22") (pinfunction "RD1_2_22") (pintype "unspecified"))
      (node (ref "U8") (pin "22") (pinfunction "RD1_2_22") (pintype "unspecified"))
    )
    (net (code "36") (name "RD1_3") (class "Default")
      (node (ref "H1") (pin "10") (pinfunction "10_10") (pintype "input"))
      (node (ref "H10") (pin "10") (pinfunction "10_10") (pintype "input"))
      (node (ref "H18") (pin "4") (pinfunction "4_4") (pintype "unspecified"))
      (node (ref "H23") (pin "4") (pinfunction "4_4") (pintype "unspecified"))
      (node (ref "RN3") (pin "1") (pinfunction "1_1") (pintype "unspecified"))
      (node (ref "U1") (pin "16") (pinfunction "RD1_3_16") (pintype "unspecified"))
      (node (ref "U2") (pin "21") (pinfunction "RD1_3_21") (pintype "unspecified"))
      (node (ref "U3") (pin "21") (pinfunction "RD1_3_21") (pintype "unspecified"))
      (node (ref "U4") (pin "21") (pinfunction "RD1_3_21") (pintype "unspecified"))
      (node (ref "U5") (pin "21") (pinfunction "RD1_3_21") (pintype "unspecified"))
      (node (ref "U6") (pin "21") (pinfunction "RD1_3_21") (pintype "unspecified"))
      (node (ref "U7") (pin "21") (pinfunction "RD1_3_21") (pintype "unspecified"))
      (node (ref "U8") (pin "21") (pinfunction "RD1_3_21") (pintype "unspecified"))
    )
    (net (code "37") (name "RD1_4") (class "Default")
      (node (ref "H1") (pin "8") (pinfunction "8_8") (pintype "input"))
      (node (ref "H10") (pin "8") (pinfunction "8_8") (pintype "input"))
      (node (ref "H18") (pin "5") (pinfunction "5_5") (pintype "unspecified"))
      (node (ref "H23") (pin "5") (pinfunction "5_5") (pintype "unspecified"))
      (node (ref "RN4") (pin "4") (pinfunction "4_4") (pintype "unspecified"))
      (node (ref "U1") (pin "15") (pinfunction "RD1_4_15") (pintype "unspecified"))
      (node (ref "U2") (pin "20") (pinfunction "RD1_4_20") (pintype "unspecified"))
      (node (ref "U3") (pin "20") (pinfunction "RD1_4_20") (pintype "unspecified"))
      (node (ref "U4") (pin "20") (pinfunction "RD1_4_20") (pintype "unspecified"))
      (node (ref "U5") (pin "20") (pinfunction "RD1_4_20") (pintype "unspecified"))
      (node (ref "U6") (pin "20") (pinfunction "RD1_4_20") (pintype "unspecified"))
      (node (ref "U7") (pin "20") (pinfunction "RD1_4_20") (pintype "unspecified"))
      (node (ref "U8") (pin "20") (pinfunction "RD1_4_20") (pintype "unspecified"))
    )
    (net (code "38") (name "RD1_5") (class "Default")
      (node (ref "H1") (pin "6") (pinfunction "6_6") (pintype "input"))
      (node (ref "H10") (pin "6") (pinfunction "6_6") (pintype "input"))
      (node (ref "H18") (pin "6") (pinfunction "6_6") (pintype "unspecified"))
      (node (ref "H23") (pin "6") (pinfunction "6_6") (pintype "unspecified"))
      (node (ref "RN4") (pin "3") (pinfunction "3_3") (pintype "unspecified"))
      (node (ref "U1") (pin "14") (pinfunction "RD1_5_14") (pintype "unspecified"))
      (node (ref "U2") (pin "19") (pinfunction "RD1_5_19") (pintype "unspecified"))
      (node (ref "U3") (pin "19") (pinfunction "RD1_5_19") (pintype "unspecified"))
      (node (ref "U4") (pin "19") (pinfunction "RD1_5_19") (pintype "unspecified"))
      (node (ref "U5") (pin "19") (pinfunction "RD1_5_19") (pintype "unspecified"))
      (node (ref "U6") (pin "19") (pinfunction "RD1_5_19") (pintype "unspecified"))
      (node (ref "U7") (pin "19") (pinfunction "RD1_5_19") (pintype "unspecified"))
      (node (ref "U8") (pin "19") (pinfunction "RD1_5_19") (pintype "unspecified"))
    )
    (net (code "39") (name "RD1_6") (class "Default")
      (node (ref "H1") (pin "4") (pinfunction "4_4") (pintype "input"))
      (node (ref "H10") (pin "4") (pinfunction "4_4") (pintype "input"))
      (node (ref "H18") (pin "7") (pinfunction "7_7") (pintype "unspecified"))
      (node (ref "H23") (pin "7") (pinfunction "7_7") (pintype "unspecified"))
      (node (ref "RN4") (pin "2") (pinfunction "2_2") (pintype "unspecified"))
      (node (ref "U1") (pin "13") (pinfunction "RD1_6_13") (pintype "unspecified"))
      (node (ref "U2") (pin "18") (pinfunction "RD1_6_18") (pintype "unspecified"))
      (node (ref "U3") (pin "18") (pinfunction "RD1_6_18") (pintype "unspecified"))
      (node (ref "U4") (pin "18") (pinfunction "RD1_6_18") (pintype "unspecified"))
      (node (ref "U5") (pin "18") (pinfunction "RD1_6_18") (pintype "unspecified"))
      (node (ref "U6") (pin "18") (pinfunction "RD1_6_18") (pintype "unspecified"))
      (node (ref "U7") (pin "18") (pinfunction "RD1_6_18") (pintype "unspecified"))
      (node (ref "U8") (pin "18") (pinfunction "RD1_6_18") (pintype "unspecified"))
    )
    (net (code "40") (name "RD1_7") (class "Default")
      (node (ref "H1") (pin "2") (pinfunction "2_2") (pintype "input"))
      (node (ref "H10") (pin "2") (pinfunction "2_2") (pintype "input"))
      (node (ref "H18") (pin "8") (pinfunction "8_8") (pintype "unspecified"))
      (node (ref "H23") (pin "8") (pinfunction "8_8") (pintype "unspecified"))
      (node (ref "RN4") (pin "1") (pinfunction "1_1") (pintype "unspecified"))
      (node (ref "U1") (pin "12") (pinfunction "RD1_7_12") (pintype "unspecified"))
      (node (ref "U2") (pin "17") (pinfunction "RD1_7_17") (pintype "unspecified"))
      (node (ref "U3") (pin "17") (pinfunction "RD1_7_17") (pintype "unspecified"))
      (node (ref "U4") (pin "17") (pinfunction "RD1_7_17") (pintype "unspecified"))
      (node (ref "U5") (pin "17") (pinfunction "RD1_7_17") (pintype "unspecified"))
      (node (ref "U6") (pin "17") (pinfunction "RD1_7_17") (pintype "unspecified"))
      (node (ref "U7") (pin "17") (pinfunction "RD1_7_17") (pintype "unspecified"))
      (node (ref "U8") (pin "17") (pinfunction "RD1_7_17") (pintype "unspecified"))
    )
    (net (code "41") (name "RD2_0") (class "Default")
      (node (ref "H1") (pin "31") (pinfunction "31_31") (pintype "input"))
      (node (ref "H10") (pin "31") (pinfunction "31_31") (pintype "input"))
      (node (ref "H19") (pin "1") (pinfunction "1_1") (pintype "unspecified"))
      (node (ref "H22") (pin "1") (pinfunction "1_1") (pintype "unspecified"))
      (node (ref "RN5") (pin "4") (pinfunction "4_4") (pintype "unspecified"))
      (node (ref "U1") (pin "27") (pinfunction "RD2_0_27") (pintype "unspecified"))
      (node (ref "U2") (pin "32") (pinfunction "RD2_0_32") (pintype "unspecified"))
      (node (ref "U3") (pin "32") (pinfunction "RD2_0_32") (pintype "unspecified"))
      (node (ref "U4") (pin "32") (pinfunction "RD2_0_32") (pintype "unspecified"))
      (node (ref "U5") (pin "32") (pinfunction "RD2_0_32") (pintype "unspecified"))
      (node (ref "U6") (pin "32") (pinfunction "RD2_0_32") (pintype "unspecified"))
      (node (ref "U7") (pin "32") (pinfunction "RD2_0_32") (pintype "unspecified"))
      (node (ref "U8") (pin "32") (pinfunction "RD2_0_32") (pintype "unspecified"))
      (node (ref "U9") (pin "23") (pinfunction "RD2_0_23") (pintype "unspecified"))
    )
    (net (code "42") (name "RD2_1") (class "Default")
      (node (ref "H1") (pin "29") (pinfunction "29_29") (pintype "input"))
      (node (ref "H10") (pin "29") (pinfunction "29_29") (pintype "input"))
      (node (ref "H19") (pin "2") (pinfunction "2_2") (pintype "unspecified"))
      (node (ref "H22") (pin "2") (pinfunction "2_2") (pintype "unspecified"))
      (node (ref "RN5") (pin "3") (pinfunction "3_3") (pintype "unspecified"))
      (node (ref "U1") (pin "26") (pinfunction "RD2_1_26") (pintype "unspecified"))
      (node (ref "U2") (pin "31") (pinfunction "RD2_1_31") (pintype "unspecified"))
      (node (ref "U3") (pin "31") (pinfunction "RD2_1_31") (pintype "unspecified"))
      (node (ref "U4") (pin "31") (pinfunction "RD2_1_31") (pintype "unspecified"))
      (node (ref "U5") (pin "31") (pinfunction "RD2_1_31") (pintype "unspecified"))
      (node (ref "U6") (pin "31") (pinfunction "RD2_1_31") (pintype "unspecified"))
      (node (ref "U7") (pin "31") (pinfunction "RD2_1_31") (pintype "unspecified"))
      (node (ref "U8") (pin "31") (pinfunction "RD2_1_31") (pintype "unspecified"))
      (node (ref "U9") (pin "24") (pinfunction "RD2_1_24") (pintype "unspecified"))
    )
    (net (code "43") (name "RD2_2") (class "Default")
      (node (ref "H1") (pin "27") (pinfunction "27_27") (pintype "input"))
      (node (ref "H10") (pin "27") (pinfunction "27_27") (pintype "input"))
      (node (ref "H19") (pin "3") (pinfunction "3_3") (pintype "unspecified"))
      (node (ref "H22") (pin "3") (pinfunction "3_3") (pintype "unspecified"))
      (node (ref "RN5") (pin "2") (pinfunction "2_2") (pintype "unspecified"))
      (node (ref "U1") (pin "25") (pinfunction "RD2_2_25") (pintype "unspecified"))
      (node (ref "U2") (pin "30") (pinfunction "RD2_2_30") (pintype "unspecified"))
      (node (ref "U3") (pin "30") (pinfunction "RD2_2_30") (pintype "unspecified"))
      (node (ref "U4") (pin "30") (pinfunction "RD2_2_30") (pintype "unspecified"))
      (node (ref "U5") (pin "30") (pinfunction "RD2_2_30") (pintype "unspecified"))
      (node (ref "U6") (pin "30") (pinfunction "RD2_2_30") (pintype "unspecified"))
      (node (ref "U7") (pin "30") (pinfunction "RD2_2_30") (pintype "unspecified"))
      (node (ref "U8") (pin "30") (pinfunction "RD2_2_30") (pintype "unspecified"))
      (node (ref "U9") (pin "25") (pinfunction "RD2_2_25") (pintype "unspecified"))
    )
    (net (code "44") (name "RD2_3") (class "Default")
      (node (ref "H1") (pin "25") (pinfunction "25_25") (pintype "input"))
      (node (ref "H10") (pin "25") (pinfunction "25_25") (pintype "input"))
      (node (ref "H19") (pin "4") (pinfunction "4_4") (pintype "unspecified"))
      (node (ref "H22") (pin "4") (pinfunction "4_4") (pintype "unspecified"))
      (node (ref "RN5") (pin "1") (pinfunction "1_1") (pintype "unspecified"))
      (node (ref "U1") (pin "24") (pinfunction "RD2_3_24") (pintype "unspecified"))
      (node (ref "U2") (pin "29") (pinfunction "RD2_3_29") (pintype "unspecified"))
      (node (ref "U3") (pin "29") (pinfunction "RD2_3_29") (pintype "unspecified"))
      (node (ref "U4") (pin "29") (pinfunction "RD2_3_29") (pintype "unspecified"))
      (node (ref "U5") (pin "29") (pinfunction "RD2_3_29") (pintype "unspecified"))
      (node (ref "U6") (pin "29") (pinfunction "RD2_3_29") (pintype "unspecified"))
      (node (ref "U7") (pin "29") (pinfunction "RD2_3_29") (pintype "unspecified"))
      (node (ref "U8") (pin "29") (pinfunction "RD2_3_29") (pintype "unspecified"))
      (node (ref "U9") (pin "26") (pinfunction "RD2_3_26") (pintype "unspecified"))
    )
    (net (code "45") (name "RD2_4") (class "Default")
      (node (ref "H1") (pin "23") (pinfunction "23_23") (pintype "input"))
      (node (ref "H10") (pin "23") (pinfunction "23_23") (pintype "input"))
      (node (ref "H19") (pin "5") (pinfunction "5_5") (pintype "unspecified"))
      (node (ref "H22") (pin "5") (pinfunction "5_5") (pintype "unspecified"))
      (node (ref "RN6") (pin "4") (pinfunction "4_4") (pintype "unspecified"))
      (node (ref "U1") (pin "23") (pinfunction "RD2_4_23") (pintype "unspecified"))
      (node (ref "U2") (pin "28") (pinfunction "RD2_4_28") (pintype "unspecified"))
      (node (ref "U3") (pin "28") (pinfunction "RD2_4_28") (pintype "unspecified"))
      (node (ref "U4") (pin "28") (pinfunction "RD2_4_28") (pintype "unspecified"))
      (node (ref "U5") (pin "28") (pinfunction "RD2_4_28") (pintype "unspecified"))
      (node (ref "U6") (pin "28") (pinfunction "RD2_4_28") (pintype "unspecified"))
      (node (ref "U7") (pin "28") (pinfunction "RD2_4_28") (pintype "unspecified"))
      (node (ref "U8") (pin "28") (pinfunction "RD2_4_28") (pintype "unspecified"))
      (node (ref "U9") (pin "27") (pinfunction "RD2_4_27") (pintype "unspecified"))
    )
    (net (code "46") (name "RD2_5") (class "Default")
      (node (ref "H1") (pin "21") (pinfunction "21_21") (pintype "input"))
      (node (ref "H10") (pin "21") (pinfunction "21_21") (pintype "input"))
      (node (ref "H19") (pin "6") (pinfunction "6_6") (pintype "unspecified"))
      (node (ref "H22") (pin "6") (pinfunction "6_6") (pintype "unspecified"))
      (node (ref "RN6") (pin "3") (pinfunction "3_3") (pintype "unspecified"))
      (node (ref "U1") (pin "22") (pinfunction "RD2_5_22") (pintype "unspecified"))
      (node (ref "U2") (pin "27") (pinfunction "RD2_5_27") (pintype "unspecified"))
      (node (ref "U3") (pin "27") (pinfunction "RD2_5_27") (pintype "unspecified"))
      (node (ref "U4") (pin "27") (pinfunction "RD2_5_27") (pintype "unspecified"))
      (node (ref "U5") (pin "27") (pinfunction "RD2_5_27") (pintype "unspecified"))
      (node (ref "U6") (pin "27") (pinfunction "RD2_5_27") (pintype "unspecified"))
      (node (ref "U7") (pin "27") (pinfunction "RD2_5_27") (pintype "unspecified"))
      (node (ref "U8") (pin "27") (pinfunction "RD2_5_27") (pintype "unspecified"))
      (node (ref "U9") (pin "28") (pinfunction "RD2_5_28") (pintype "unspecified"))
    )
    (net (code "47") (name "RD2_6") (class "Default")
      (node (ref "H1") (pin "19") (pinfunction "19_19") (pintype "input"))
      (node (ref "H10") (pin "19") (pinfunction "19_19") (pintype "input"))
      (node (ref "H19") (pin "7") (pinfunction "7_7") (pintype "unspecified"))
      (node (ref "H22") (pin "7") (pinfunction "7_7") (pintype "unspecified"))
      (node (ref "RN6") (pin "2") (pinfunction "2_2") (pintype "unspecified"))
      (node (ref "U1") (pin "21") (pinfunction "RD2_6_21") (pintype "unspecified"))
      (node (ref "U2") (pin "26") (pinfunction "RD2_6_26") (pintype "unspecified"))
      (node (ref "U3") (pin "26") (pinfunction "RD2_6_26") (pintype "unspecified"))
      (node (ref "U4") (pin "26") (pinfunction "RD2_6_26") (pintype "unspecified"))
      (node (ref "U5") (pin "26") (pinfunction "RD2_6_26") (pintype "unspecified"))
      (node (ref "U6") (pin "26") (pinfunction "RD2_6_26") (pintype "unspecified"))
      (node (ref "U7") (pin "26") (pinfunction "RD2_6_26") (pintype "unspecified"))
      (node (ref "U8") (pin "26") (pinfunction "RD2_6_26") (pintype "unspecified"))
      (node (ref "U9") (pin "29") (pinfunction "RD2_6_29") (pintype "unspecified"))
    )
    (net (code "48") (name "RD2_7") (class "Default")
      (node (ref "H1") (pin "17") (pinfunction "17_17") (pintype "input"))
      (node (ref "H10") (pin "17") (pinfunction "17_17") (pintype "input"))
      (node (ref "H19") (pin "8") (pinfunction "8_8") (pintype "unspecified"))
      (node (ref "H22") (pin "8") (pinfunction "8_8") (pintype "unspecified"))
      (node (ref "RN6") (pin "1") (pinfunction "1_1") (pintype "unspecified"))
      (node (ref "U1") (pin "20") (pinfunction "RD2_7_20") (pintype "unspecified"))
      (node (ref "U2") (pin "25") (pinfunction "RD2_7_25") (pintype "unspecified"))
      (node (ref "U3") (pin "25") (pinfunction "RD2_7_25") (pintype "unspecified"))
      (node (ref "U4") (pin "25") (pinfunction "RD2_7_25") (pintype "unspecified"))
      (node (ref "U5") (pin "25") (pinfunction "RD2_7_25") (pintype "unspecified"))
      (node (ref "U6") (pin "25") (pinfunction "RD2_7_25") (pintype "unspecified"))
      (node (ref "U7") (pin "25") (pinfunction "RD2_7_25") (pintype "unspecified"))
      (node (ref "U8") (pin "25") (pinfunction "RD2_7_25") (pintype "unspecified"))
      (node (ref "U9") (pin "30") (pinfunction "RD2_7_30") (pintype "unspecified"))
    )
    (net (code "49") (name "RD3_0") (class "Default")
      (node (ref "H1") (pin "32") (pinfunction "32_32") (pintype "input"))
      (node (ref "H10") (pin "32") (pinfunction "32_32") (pintype "input"))
      (node (ref "H20") (pin "1") (pinfunction "1_1") (pintype "unspecified"))
      (node (ref "H21") (pin "1") (pinfunction "1_1") (pintype "unspecified"))
      (node (ref "RN7") (pin "4") (pinfunction "4_4") (pintype "unspecified"))
      (node (ref "U1") (pin "35") (pinfunction "RD3_0_35") (pintype "unspecified"))
      (node (ref "U2") (pin "40") (pinfunction "RD3_0_40") (pintype "unspecified"))
      (node (ref "U3") (pin "40") (pinfunction "RD3_0_40") (pintype "unspecified"))
      (node (ref "U4") (pin "40") (pinfunction "RD3_0_40") (pintype "unspecified"))
      (node (ref "U5") (pin "40") (pinfunction "RD3_0_40") (pintype "unspecified"))
      (node (ref "U6") (pin "40") (pinfunction "RD3_0_40") (pintype "unspecified"))
      (node (ref "U7") (pin "40") (pinfunction "RD3_0_40") (pintype "unspecified"))
      (node (ref "U8") (pin "40") (pinfunction "RD3_0_40") (pintype "unspecified"))
    )
    (net (code "50") (name "RD3_1") (class "Default")
      (node (ref "H1") (pin "30") (pinfunction "30_30") (pintype "input"))
      (node (ref "H10") (pin "30") (pinfunction "30_30") (pintype "input"))
      (node (ref "H20") (pin "2") (pinfunction "2_2") (pintype "unspecified"))
      (node (ref "H21") (pin "2") (pinfunction "2_2") (pintype "unspecified"))
      (node (ref "RN7") (pin "3") (pinfunction "3_3") (pintype "unspecified"))
      (node (ref "U1") (pin "34") (pinfunction "RD3_1_34") (pintype "unspecified"))
      (node (ref "U2") (pin "39") (pinfunction "RD3_1_39") (pintype "unspecified"))
      (node (ref "U3") (pin "39") (pinfunction "RD3_1_39") (pintype "unspecified"))
      (node (ref "U4") (pin "39") (pinfunction "RD3_1_39") (pintype "unspecified"))
      (node (ref "U5") (pin "39") (pinfunction "RD3_1_39") (pintype "unspecified"))
      (node (ref "U6") (pin "39") (pinfunction "RD3_1_39") (pintype "unspecified"))
      (node (ref "U7") (pin "39") (pinfunction "RD3_1_39") (pintype "unspecified"))
      (node (ref "U8") (pin "39") (pinfunction "RD3_1_39") (pintype "unspecified"))
    )
    (net (code "51") (name "RD3_2") (class "Default")
      (node (ref "H1") (pin "28") (pinfunction "28_28") (pintype "input"))
      (node (ref "H10") (pin "28") (pinfunction "28_28") (pintype "input"))
      (node (ref "H20") (pin "3") (pinfunction "3_3") (pintype "unspecified"))
      (node (ref "H21") (pin "3") (pinfunction "3_3") (pintype "unspecified"))
      (node (ref "RN7") (pin "2") (pinfunction "2_2") (pintype "unspecified"))
      (node (ref "U1") (pin "33") (pinfunction "RD3_2_33") (pintype "unspecified"))
      (node (ref "U2") (pin "38") (pinfunction "RD3_2_38") (pintype "unspecified"))
      (node (ref "U3") (pin "38") (pinfunction "RD3_2_38") (pintype "unspecified"))
      (node (ref "U4") (pin "38") (pinfunction "RD3_2_38") (pintype "unspecified"))
      (node (ref "U5") (pin "38") (pinfunction "RD3_2_38") (pintype "unspecified"))
      (node (ref "U6") (pin "38") (pinfunction "RD3_2_38") (pintype "unspecified"))
      (node (ref "U7") (pin "38") (pinfunction "RD3_2_38") (pintype "unspecified"))
      (node (ref "U8") (pin "38") (pinfunction "RD3_2_38") (pintype "unspecified"))
    )
    (net (code "52") (name "RD3_3") (class "Default")
      (node (ref "H1") (pin "26") (pinfunction "26_26") (pintype "input"))
      (node (ref "H10") (pin "26") (pinfunction "26_26") (pintype "input"))
      (node (ref "H20") (pin "4") (pinfunction "4_4") (pintype "unspecified"))
      (node (ref "H21") (pin "4") (pinfunction "4_4") (pintype "unspecified"))
      (node (ref "RN7") (pin "1") (pinfunction "1_1") (pintype "unspecified"))
      (node (ref "U1") (pin "32") (pinfunction "RD3_3_32") (pintype "unspecified"))
      (node (ref "U2") (pin "37") (pinfunction "RD3_3_37") (pintype "unspecified"))
      (node (ref "U3") (pin "37") (pinfunction "RD3_3_37") (pintype "unspecified"))
      (node (ref "U4") (pin "37") (pinfunction "RD3_3_37") (pintype "unspecified"))
      (node (ref "U5") (pin "37") (pinfunction "RD3_3_37") (pintype "unspecified"))
      (node (ref "U6") (pin "37") (pinfunction "RD3_3_37") (pintype "unspecified"))
      (node (ref "U7") (pin "37") (pinfunction "RD3_3_37") (pintype "unspecified"))
      (node (ref "U8") (pin "37") (pinfunction "RD3_3_37") (pintype "unspecified"))
    )
    (net (code "53") (name "RD3_4") (class "Default")
      (node (ref "H1") (pin "24") (pinfunction "24_24") (pintype "input"))
      (node (ref "H10") (pin "24") (pinfunction "24_24") (pintype "input"))
      (node (ref "H20") (pin "5") (pinfunction "5_5") (pintype "unspecified"))
      (node (ref "H21") (pin "5") (pinfunction "5_5") (pintype "unspecified"))
      (node (ref "RN8") (pin "4") (pinfunction "4_4") (pintype "unspecified"))
      (node (ref "U1") (pin "31") (pinfunction "RD3_4_31") (pintype "unspecified"))
      (node (ref "U2") (pin "36") (pinfunction "RD3_4_36") (pintype "unspecified"))
      (node (ref "U3") (pin "36") (pinfunction "RD3_4_36") (pintype "unspecified"))
      (node (ref "U4") (pin "36") (pinfunction "RD3_4_36") (pintype "unspecified"))
      (node (ref "U5") (pin "36") (pinfunction "RD3_4_36") (pintype "unspecified"))
      (node (ref "U6") (pin "36") (pinfunction "RD3_4_36") (pintype "unspecified"))
      (node (ref "U7") (pin "36") (pinfunction "RD3_4_36") (pintype "unspecified"))
      (node (ref "U8") (pin "36") (pinfunction "RD3_4_36") (pintype "unspecified"))
    )
    (net (code "54") (name "RD3_5") (class "Default")
      (node (ref "H1") (pin "22") (pinfunction "22_22") (pintype "input"))
      (node (ref "H10") (pin "22") (pinfunction "22_22") (pintype "input"))
      (node (ref "H20") (pin "6") (pinfunction "6_6") (pintype "unspecified"))
      (node (ref "H21") (pin "6") (pinfunction "6_6") (pintype "unspecified"))
      (node (ref "RN8") (pin "3") (pinfunction "3_3") (pintype "unspecified"))
      (node (ref "U1") (pin "30") (pinfunction "RD3_5_30") (pintype "unspecified"))
      (node (ref "U2") (pin "35") (pinfunction "RD3_5_35") (pintype "unspecified"))
      (node (ref "U3") (pin "35") (pinfunction "RD3_5_35") (pintype "unspecified"))
      (node (ref "U4") (pin "35") (pinfunction "RD3_5_35") (pintype "unspecified"))
      (node (ref "U5") (pin "35") (pinfunction "RD3_5_35") (pintype "unspecified"))
      (node (ref "U6") (pin "35") (pinfunction "RD3_5_35") (pintype "unspecified"))
      (node (ref "U7") (pin "35") (pinfunction "RD3_5_35") (pintype "unspecified"))
      (node (ref "U8") (pin "35") (pinfunction "RD3_5_35") (pintype "unspecified"))
    )
    (net (code "55") (name "RD3_6") (class "Default")
      (node (ref "H1") (pin "20") (pinfunction "20_20") (pintype "input"))
      (node (ref "H10") (pin "20") (pinfunction "20_20") (pintype "input"))
      (node (ref "H20") (pin "7") (pinfunction "7_7") (pintype "unspecified"))
      (node (ref "H21") (pin "7") (pinfunction "7_7") (pintype "unspecified"))
      (node (ref "RN8") (pin "2") (pinfunction "2_2") (pintype "unspecified"))
      (node (ref "U1") (pin "29") (pinfunction "RD3_6_29") (pintype "unspecified"))
      (node (ref "U2") (pin "34") (pinfunction "RD3_6_34") (pintype "unspecified"))
      (node (ref "U3") (pin "34") (pinfunction "RD3_6_34") (pintype "unspecified"))
      (node (ref "U4") (pin "34") (pinfunction "RD3_6_34") (pintype "unspecified"))
      (node (ref "U5") (pin "34") (pinfunction "RD3_6_34") (pintype "unspecified"))
      (node (ref "U6") (pin "34") (pinfunction "RD3_6_34") (pintype "unspecified"))
      (node (ref "U7") (pin "34") (pinfunction "RD3_6_34") (pintype "unspecified"))
      (node (ref "U8") (pin "34") (pinfunction "RD3_6_34") (pintype "unspecified"))
    )
    (net (code "56") (name "RD3_7") (class "Default")
      (node (ref "H1") (pin "18") (pinfunction "18_18") (pintype "input"))
      (node (ref "H10") (pin "18") (pinfunction "18_18") (pintype "input"))
      (node (ref "H20") (pin "8") (pinfunction "8_8") (pintype "unspecified"))
      (node (ref "H21") (pin "8") (pinfunction "8_8") (pintype "unspecified"))
      (node (ref "RN8") (pin "1") (pinfunction "1_1") (pintype "unspecified"))
      (node (ref "U1") (pin "28") (pinfunction "RD3_7_28") (pintype "unspecified"))
      (node (ref "U2") (pin "33") (pinfunction "RD3_7_33") (pintype "unspecified"))
      (node (ref "U3") (pin "33") (pinfunction "RD3_7_33") (pintype "unspecified"))
      (node (ref "U4") (pin "33") (pinfunction "RD3_7_33") (pintype "unspecified"))
      (node (ref "U5") (pin "33") (pinfunction "RD3_7_33") (pintype "unspecified"))
      (node (ref "U6") (pin "33") (pinfunction "RD3_7_33") (pintype "unspecified"))
      (node (ref "U7") (pin "33") (pinfunction "RD3_7_33") (pintype "unspecified"))
      (node (ref "U8") (pin "33") (pinfunction "RD3_7_33") (pintype "unspecified"))
    )
    (net (code "57") (name "RE1#") (class "Default")
      (node (ref "H2") (pin "14") (pinfunction "14_14") (pintype "input"))
      (node (ref "H9") (pin "14") (pinfunction "14_14") (pintype "input"))
      (node (ref "U11") (pin "4") (pinfunction "G#2A_4") (pintype "unspecified"))
    )
    (net (code "58") (name "RE1#0") (class "Default")
      (node (ref "U11") (pin "14") (pinfunction "Y1_14") (pintype "unspecified"))
      (node (ref "U2") (pin "2") (pinfunction "RE1#_2") (pintype "unspecified"))
    )
    (net (code "59") (name "RE1#1") (class "Default")
      (node (ref "U11") (pin "13") (pinfunction "Y2_13") (pintype "unspecified"))
      (node (ref "U3") (pin "2") (pinfunction "RE1#_2") (pintype "unspecified"))
    )
    (net (code "60") (name "RE1#2") (class "Default")
      (node (ref "U11") (pin "12") (pinfunction "Y3_12") (pintype "unspecified"))
      (node (ref "U4") (pin "2") (pinfunction "RE1#_2") (pintype "unspecified"))
    )
    (net (code "61") (name "RE1#3") (class "Default")
      (node (ref "U11") (pin "11") (pinfunction "Y4_11") (pintype "unspecified"))
      (node (ref "U5") (pin "2") (pinfunction "RE1#_2") (pintype "unspecified"))
    )
    (net (code "62") (name "RE1#4") (class "Default")
      (node (ref "U11") (pin "10") (pinfunction "Y5_10") (pintype "unspecified"))
      (node (ref "U6") (pin "2") (pinfunction "RE1#_2") (pintype "unspecified"))
    )
    (net (code "63") (name "RE1#5") (class "Default")
      (node (ref "U11") (pin "9") (pinfunction "Y6_9") (pintype "unspecified"))
      (node (ref "U7") (pin "2") (pinfunction "RE1#_2") (pintype "unspecified"))
    )
    (net (code "64") (name "RE1#6") (class "Default")
      (node (ref "U11") (pin "7") (pinfunction "Y7_7") (pintype "unspecified"))
      (node (ref "U8") (pin "2") (pinfunction "RE1#_2") (pintype "unspecified"))
    )
    (net (code "65") (name "RE2#") (class "Default")
      (node (ref "H2") (pin "16") (pinfunction "16_16") (pintype "input"))
      (node (ref "H9") (pin "16") (pinfunction "16_16") (pintype "input"))
      (node (ref "U12") (pin "4") (pinfunction "G#2A_4") (pintype "unspecified"))
      (node (ref "U9") (pin "2") (pinfunction "ImmOE2#_2") (pintype "unspecified"))
    )
    (net (code "66") (name "RE2#0") (class "Default")
      (node (ref "U12") (pin "14") (pinfunction "Y1_14") (pintype "unspecified"))
      (node (ref "U2") (pin "3") (pinfunction "RE2#_3") (pintype "unspecified"))
      (node (ref "U3") (pin "4") (pinfunction "RE3#_4") (pintype "unspecified"))
    )
    (net (code "67") (name "RE2#1") (class "Default")
      (node (ref "U12") (pin "13") (pinfunction "Y2_13") (pintype "unspecified"))
      (node (ref "U3") (pin "3") (pinfunction "RE2#_3") (pintype "unspecified"))
      (node (ref "U4") (pin "4") (pinfunction "RE3#_4") (pintype "unspecified"))
    )
    (net (code "68") (name "RE2#2") (class "Default")
      (node (ref "U12") (pin "12") (pinfunction "Y3_12") (pintype "unspecified"))
      (node (ref "U4") (pin "3") (pinfunction "RE2#_3") (pintype "unspecified"))
      (node (ref "U5") (pin "4") (pinfunction "RE3#_4") (pintype "unspecified"))
    )
    (net (code "69") (name "RE2#3") (class "Default")
      (node (ref "U12") (pin "11") (pinfunction "Y4_11") (pintype "unspecified"))
      (node (ref "U5") (pin "3") (pinfunction "RE2#_3") (pintype "unspecified"))
      (node (ref "U6") (pin "4") (pinfunction "RE3#_4") (pintype "unspecified"))
    )
    (net (code "70") (name "RE2#4") (class "Default")
      (node (ref "U12") (pin "10") (pinfunction "Y5_10") (pintype "unspecified"))
      (node (ref "U6") (pin "3") (pinfunction "RE2#_3") (pintype "unspecified"))
      (node (ref "U7") (pin "4") (pinfunction "RE3#_4") (pintype "unspecified"))
    )
    (net (code "71") (name "RE2#5") (class "Default")
      (node (ref "U12") (pin "9") (pinfunction "Y6_9") (pintype "unspecified"))
      (node (ref "U7") (pin "3") (pinfunction "RE2#_3") (pintype "unspecified"))
      (node (ref "U8") (pin "4") (pinfunction "RE3#_4") (pintype "unspecified"))
    )
    (net (code "72") (name "RE2#6") (class "Default")
      (node (ref "U12") (pin "7") (pinfunction "Y7_7") (pintype "unspecified"))
      (node (ref "U8") (pin "3") (pinfunction "RE2#_3") (pintype "unspecified"))
    )
    (net (code "73") (name "Reset") (class "Default")
      (node (ref "H11") (pin "4") (pinfunction "4_4") (pintype "unspecified"))
      (node (ref "H12") (pin "4") (pinfunction "4_4") (pintype "unspecified"))
      (node (ref "H13") (pin "4") (pinfunction "4_4") (pintype "unspecified"))
      (node (ref "H14") (pin "4") (pinfunction "4_4") (pintype "unspecified"))
      (node (ref "H15") (pin "4") (pinfunction "4_4") (pintype "unspecified"))
      (node (ref "H16") (pin "4") (pinfunction "4_4") (pintype "unspecified"))
    )
    (net (code "74") (name "RootClk") (class "Default")
      (node (ref "H11") (pin "3") (pinfunction "3_3") (pintype "unspecified"))
      (node (ref "H12") (pin "3") (pinfunction "3_3") (pintype "unspecified"))
      (node (ref "H13") (pin "3") (pinfunction "3_3") (pintype "unspecified"))
      (node (ref "H14") (pin "3") (pinfunction "3_3") (pintype "unspecified"))
      (node (ref "H15") (pin "3") (pinfunction "3_3") (pintype "unspecified"))
      (node (ref "H16") (pin "3") (pinfunction "3_3") (pintype "unspecified"))
      (node (ref "U13") (pin "2") (pinfunction "A_2") (pintype "unspecified"))
      (node (ref "U14") (pin "2") (pinfunction "A_2") (pintype "unspecified"))
    )
    (net (code "75") (name "VCC") (class "Default")
      (node (ref "C1") (pin "1") (pinfunction "1_1") (pintype "unspecified"))
      (node (ref "C2") (pin "1") (pinfunction "1_1") (pintype "unspecified"))
      (node (ref "C3") (pin "1") (pinfunction "1_1") (pintype "unspecified"))
      (node (ref "C4") (pin "1") (pinfunction "1_1") (pintype "unspecified"))
      (node (ref "C5") (pin "1") (pinfunction "1_1") (pintype "unspecified"))
      (node (ref "H11") (pin "1") (pinfunction "1_1") (pintype "unspecified"))
      (node (ref "H12") (pin "1") (pinfunction "1_1") (pintype "unspecified"))
      (node (ref "H13") (pin "1") (pinfunction "1_1") (pintype "unspecified"))
      (node (ref "H14") (pin "1") (pinfunction "1_1") (pintype "unspecified"))
      (node (ref "H15") (pin "1") (pinfunction "1_1") (pintype "unspecified"))
      (node (ref "H16") (pin "1") (pinfunction "1_1") (pintype "unspecified"))
      (node (ref "H29") (pin "1") (pinfunction "1_1") (pintype "input"))
      (node (ref "H30") (pin "1") (pinfunction "1_1") (pintype "input"))
      (node (ref "R1") (pin "2") (pinfunction "2_2") (pintype "unspecified"))
      (node (ref "U1") (pin "11") (pinfunction "VDD_11") (pintype "unspecified"))
      (node (ref "U10") (pin "16") (pinfunction "VCC_16") (pintype "unspecified"))
      (node (ref "U10") (pin "6") (pinfunction "G1_6") (pintype "unspecified"))
      (node (ref "U11") (pin "16") (pinfunction "VCC_16") (pintype "unspecified"))
      (node (ref "U11") (pin "6") (pinfunction "G1_6") (pintype "unspecified"))
      (node (ref "U12") (pin "16") (pinfunction "VCC_16") (pintype "unspecified"))
      (node (ref "U12") (pin "6") (pinfunction "G1_6") (pintype "unspecified"))
      (node (ref "U13") (pin "5") (pinfunction "VCC_5") (pintype "unspecified"))
      (node (ref "U14") (pin "5") (pinfunction "VCC_5") (pintype "unspecified"))
      (node (ref "U2") (pin "16") (pinfunction "VDD_16") (pintype "unspecified"))
      (node (ref "U2") (pin "4") (pinfunction "RE3#_4") (pintype "unspecified"))
      (node (ref "U3") (pin "16") (pinfunction "VDD_16") (pintype "unspecified"))
      (node (ref "U4") (pin "16") (pinfunction "VDD_16") (pintype "unspecified"))
      (node (ref "U5") (pin "16") (pinfunction "VDD_16") (pintype "unspecified"))
      (node (ref "U6") (pin "16") (pinfunction "VDD_16") (pintype "unspecified"))
      (node (ref "U7") (pin "16") (pinfunction "VDD_16") (pintype "unspecified"))
      (node (ref "U8") (pin "16") (pinfunction "VDD_16") (pintype "unspecified"))
      (node (ref "U9") (pin "31") (pinfunction "VDD_31") (pintype "unspecified"))
      (node (ref "U9") (pin "4") (pinfunction "MoveOE1_4") (pintype "unspecified"))
      (node (ref "USB1") (pin "A9") (pinfunction "VBUS_A9") (pintype "unspecified"))
      (node (ref "USB1") (pin "B9") (pinfunction "VBUS_B9") (pintype "unspecified"))
    )
    (net (code "76") (name "WA0") (class "Default")
      (node (ref "H2") (pin "7") (pinfunction "7_7") (pintype "input"))
      (node (ref "H9") (pin "7") (pinfunction "7_7") (pintype "input"))
      (node (ref "U10") (pin "1") (pinfunction "A_1") (pintype "unspecified"))
    )
    (net (code "77") (name "WA1") (class "Default")
      (node (ref "H2") (pin "5") (pinfunction "5_5") (pintype "input"))
      (node (ref "H9") (pin "5") (pinfunction "5_5") (pintype "input"))
      (node (ref "U10") (pin "2") (pinfunction "B_2") (pintype "unspecified"))
    )
    (net (code "78") (name "WA2") (class "Default")
      (node (ref "H2") (pin "3") (pinfunction "3_3") (pintype "input"))
      (node (ref "H9") (pin "3") (pinfunction "3_3") (pintype "input"))
      (node (ref "U10") (pin "3") (pinfunction "C_3") (pintype "unspecified"))
    )
    (net (code "79") (name "WD0") (class "Default")
      (node (ref "H1") (pin "15") (pinfunction "15_15") (pintype "input"))
      (node (ref "H10") (pin "15") (pinfunction "15_15") (pintype "input"))
      (node (ref "H17") (pin "1") (pinfunction "1_1") (pintype "unspecified"))
      (node (ref "H24") (pin "1") (pinfunction "1_1") (pintype "unspecified"))
      (node (ref "RN2") (pin "4") (pinfunction "4_4") (pintype "unspecified"))
      (node (ref "U1") (pin "8") (pinfunction "WD0_8") (pintype "unspecified"))
      (node (ref "U2") (pin "13") (pinfunction "WD0_13") (pintype "unspecified"))
      (node (ref "U3") (pin "13") (pinfunction "WD0_13") (pintype "unspecified"))
      (node (ref "U4") (pin "13") (pinfunction "WD0_13") (pintype "unspecified"))
      (node (ref "U5") (pin "13") (pinfunction "WD0_13") (pintype "unspecified"))
      (node (ref "U6") (pin "13") (pinfunction "WD0_13") (pintype "unspecified"))
      (node (ref "U7") (pin "13") (pinfunction "WD0_13") (pintype "unspecified"))
      (node (ref "U8") (pin "13") (pinfunction "WD0_13") (pintype "unspecified"))
      (node (ref "U9") (pin "34") (pinfunction "WD0_34") (pintype "unspecified"))
    )
    (net (code "80") (name "WD1") (class "Default")
      (node (ref "H1") (pin "13") (pinfunction "13_13") (pintype "input"))
      (node (ref "H10") (pin "13") (pinfunction "13_13") (pintype "input"))
      (node (ref "H17") (pin "2") (pinfunction "2_2") (pintype "unspecified"))
      (node (ref "H24") (pin "2") (pinfunction "2_2") (pintype "unspecified"))
      (node (ref "RN2") (pin "3") (pinfunction "3_3") (pintype "unspecified"))
      (node (ref "U1") (pin "7") (pinfunction "WD1_7") (pintype "unspecified"))
      (node (ref "U2") (pin "12") (pinfunction "WD1_12") (pintype "unspecified"))
      (node (ref "U3") (pin "12") (pinfunction "WD1_12") (pintype "unspecified"))
      (node (ref "U4") (pin "12") (pinfunction "WD1_12") (pintype "unspecified"))
      (node (ref "U5") (pin "12") (pinfunction "WD1_12") (pintype "unspecified"))
      (node (ref "U6") (pin "12") (pinfunction "WD1_12") (pintype "unspecified"))
      (node (ref "U7") (pin "12") (pinfunction "WD1_12") (pintype "unspecified"))
      (node (ref "U8") (pin "12") (pinfunction "WD1_12") (pintype "unspecified"))
      (node (ref "U9") (pin "35") (pinfunction "WD1_35") (pintype "unspecified"))
    )
    (net (code "81") (name "WD2") (class "Default")
      (node (ref "H1") (pin "11") (pinfunction "11_11") (pintype "input"))
      (node (ref "H10") (pin "11") (pinfunction "11_11") (pintype "input"))
      (node (ref "H17") (pin "3") (pinfunction "3_3") (pintype "unspecified"))
      (node (ref "H24") (pin "3") (pinfunction "3_3") (pintype "unspecified"))
      (node (ref "RN2") (pin "2") (pinfunction "2_2") (pintype "unspecified"))
      (node (ref "U1") (pin "6") (pinfunction "WD2_6") (pintype "unspecified"))
      (node (ref "U2") (pin "11") (pinfunction "WD2_11") (pintype "unspecified"))
      (node (ref "U3") (pin "11") (pinfunction "WD2_11") (pintype "unspecified"))
      (node (ref "U4") (pin "11") (pinfunction "WD2_11") (pintype "unspecified"))
      (node (ref "U5") (pin "11") (pinfunction "WD2_11") (pintype "unspecified"))
      (node (ref "U6") (pin "11") (pinfunction "WD2_11") (pintype "unspecified"))
      (node (ref "U7") (pin "11") (pinfunction "WD2_11") (pintype "unspecified"))
      (node (ref "U8") (pin "11") (pinfunction "WD2_11") (pintype "unspecified"))
      (node (ref "U9") (pin "36") (pinfunction "WD2_36") (pintype "unspecified"))
    )
    (net (code "82") (name "WD3") (class "Default")
      (node (ref "H1") (pin "9") (pinfunction "9_9") (pintype "input"))
      (node (ref "H10") (pin "9") (pinfunction "9_9") (pintype "input"))
      (node (ref "H17") (pin "4") (pinfunction "4_4") (pintype "unspecified"))
      (node (ref "H24") (pin "4") (pinfunction "4_4") (pintype "unspecified"))
      (node (ref "RN2") (pin "1") (pinfunction "1_1") (pintype "unspecified"))
      (node (ref "U1") (pin "5") (pinfunction "WD3_5") (pintype "unspecified"))
      (node (ref "U2") (pin "10") (pinfunction "WD3_10") (pintype "unspecified"))
      (node (ref "U3") (pin "10") (pinfunction "WD3_10") (pintype "unspecified"))
      (node (ref "U4") (pin "10") (pinfunction "WD3_10") (pintype "unspecified"))
      (node (ref "U5") (pin "10") (pinfunction "WD3_10") (pintype "unspecified"))
      (node (ref "U6") (pin "10") (pinfunction "WD3_10") (pintype "unspecified"))
      (node (ref "U7") (pin "10") (pinfunction "WD3_10") (pintype "unspecified"))
      (node (ref "U8") (pin "10") (pinfunction "WD3_10") (pintype "unspecified"))
      (node (ref "U9") (pin "37") (pinfunction "WD3_37") (pintype "unspecified"))
    )
    (net (code "83") (name "WD4") (class "Default")
      (node (ref "H1") (pin "7") (pinfunction "7_7") (pintype "input"))
      (node (ref "H10") (pin "7") (pinfunction "7_7") (pintype "input"))
      (node (ref "H17") (pin "5") (pinfunction "5_5") (pintype "unspecified"))
      (node (ref "H24") (pin "5") (pinfunction "5_5") (pintype "unspecified"))
      (node (ref "RN1") (pin "4") (pinfunction "4_4") (pintype "unspecified"))
      (node (ref "U1") (pin "4") (pinfunction "WD4_4") (pintype "unspecified"))
      (node (ref "U2") (pin "9") (pinfunction "WD4_9") (pintype "unspecified"))
      (node (ref "U3") (pin "9") (pinfunction "WD4_9") (pintype "unspecified"))
      (node (ref "U4") (pin "9") (pinfunction "WD4_9") (pintype "unspecified"))
      (node (ref "U5") (pin "9") (pinfunction "WD4_9") (pintype "unspecified"))
      (node (ref "U6") (pin "9") (pinfunction "WD4_9") (pintype "unspecified"))
      (node (ref "U7") (pin "9") (pinfunction "WD4_9") (pintype "unspecified"))
      (node (ref "U8") (pin "9") (pinfunction "WD4_9") (pintype "unspecified"))
      (node (ref "U9") (pin "38") (pinfunction "WD4_38") (pintype "unspecified"))
    )
    (net (code "84") (name "WD5") (class "Default")
      (node (ref "H1") (pin "5") (pinfunction "5_5") (pintype "input"))
      (node (ref "H10") (pin "5") (pinfunction "5_5") (pintype "input"))
      (node (ref "H17") (pin "6") (pinfunction "6_6") (pintype "unspecified"))
      (node (ref "H24") (pin "6") (pinfunction "6_6") (pintype "unspecified"))
      (node (ref "RN1") (pin "3") (pinfunction "3_3") (pintype "unspecified"))
      (node (ref "U1") (pin "3") (pinfunction "WD5_3") (pintype "unspecified"))
      (node (ref "U2") (pin "8") (pinfunction "WD5_8") (pintype "unspecified"))
      (node (ref "U3") (pin "8") (pinfunction "WD5_8") (pintype "unspecified"))
      (node (ref "U4") (pin "8") (pinfunction "WD5_8") (pintype "unspecified"))
      (node (ref "U5") (pin "8") (pinfunction "WD5_8") (pintype "unspecified"))
      (node (ref "U6") (pin "8") (pinfunction "WD5_8") (pintype "unspecified"))
      (node (ref "U7") (pin "8") (pinfunction "WD5_8") (pintype "unspecified"))
      (node (ref "U8") (pin "8") (pinfunction "WD5_8") (pintype "unspecified"))
      (node (ref "U9") (pin "39") (pinfunction "WD5_39") (pintype "unspecified"))
    )
    (net (code "85") (name "WD6") (class "Default")
      (node (ref "H1") (pin "3") (pinfunction "3_3") (pintype "input"))
      (node (ref "H10") (pin "3") (pinfunction "3_3") (pintype "input"))
      (node (ref "H17") (pin "7") (pinfunction "7_7") (pintype "unspecified"))
      (node (ref "H24") (pin "7") (pinfunction "7_7") (pintype "unspecified"))
      (node (ref "RN1") (pin "2") (pinfunction "2_2") (pintype "unspecified"))
      (node (ref "U1") (pin "2") (pinfunction "WD6_2") (pintype "unspecified"))
      (node (ref "U2") (pin "7") (pinfunction "WD6_7") (pintype "unspecified"))
      (node (ref "U3") (pin "7") (pinfunction "WD6_7") (pintype "unspecified"))
      (node (ref "U4") (pin "7") (pinfunction "WD6_7") (pintype "unspecified"))
      (node (ref "U5") (pin "7") (pinfunction "WD6_7") (pintype "unspecified"))
      (node (ref "U6") (pin "7") (pinfunction "WD6_7") (pintype "unspecified"))
      (node (ref "U7") (pin "7") (pinfunction "WD6_7") (pintype "unspecified"))
      (node (ref "U8") (pin "7") (pinfunction "WD6_7") (pintype "unspecified"))
      (node (ref "U9") (pin "40") (pinfunction "WD6_40") (pintype "unspecified"))
    )
    (net (code "86") (name "WD7") (class "Default")
      (node (ref "H1") (pin "1") (pinfunction "1_1") (pintype "input"))
      (node (ref "H10") (pin "1") (pinfunction "1_1") (pintype "input"))
      (node (ref "H17") (pin "8") (pinfunction "8_8") (pintype "unspecified"))
      (node (ref "H24") (pin "8") (pinfunction "8_8") (pintype "unspecified"))
      (node (ref "RN1") (pin "1") (pinfunction "1_1") (pintype "unspecified"))
      (node (ref "U1") (pin "1") (pinfunction "WD7_1") (pintype "unspecified"))
      (node (ref "U2") (pin "6") (pinfunction "WD7_6") (pintype "unspecified"))
      (node (ref "U3") (pin "6") (pinfunction "WD7_6") (pintype "unspecified"))
      (node (ref "U4") (pin "6") (pinfunction "WD7_6") (pintype "unspecified"))
      (node (ref "U5") (pin "6") (pinfunction "WD7_6") (pintype "unspecified"))
      (node (ref "U6") (pin "6") (pinfunction "WD7_6") (pintype "unspecified"))
      (node (ref "U7") (pin "6") (pinfunction "WD7_6") (pintype "unspecified"))
      (node (ref "U8") (pin "6") (pinfunction "WD7_6") (pintype "unspecified"))
      (node (ref "U9") (pin "41") (pinfunction "WD7_41") (pintype "unspecified"))
    )
    (net (code "87") (name "WE#") (class "Default")
      (node (ref "H2") (pin "12") (pinfunction "12_12") (pintype "input"))
      (node (ref "H9") (pin "12") (pinfunction "12_12") (pintype "input"))
      (node (ref "U10") (pin "4") (pinfunction "G#2A_4") (pintype "unspecified"))
    )
    (net (code "88") (name "WE#0") (class "Default")
      (node (ref "U10") (pin "14") (pinfunction "Y1_14") (pintype "unspecified"))
      (node (ref "U2") (pin "1") (pinfunction "WE#_1") (pintype "unspecified"))
    )
    (net (code "89") (name "WE#1") (class "Default")
      (node (ref "U10") (pin "13") (pinfunction "Y2_13") (pintype "unspecified"))
      (node (ref "U3") (pin "1") (pinfunction "WE#_1") (pintype "unspecified"))
    )
    (net (code "90") (name "WE#2") (class "Default")
      (node (ref "U10") (pin "12") (pinfunction "Y3_12") (pintype "unspecified"))
      (node (ref "U4") (pin "1") (pinfunction "WE#_1") (pintype "unspecified"))
    )
    (net (code "91") (name "WE#3") (class "Default")
      (node (ref "U10") (pin "11") (pinfunction "Y4_11") (pintype "unspecified"))
      (node (ref "U5") (pin "1") (pinfunction "WE#_1") (pintype "unspecified"))
    )
    (net (code "92") (name "WE#4") (class "Default")
      (node (ref "U10") (pin "10") (pinfunction "Y5_10") (pintype "unspecified"))
      (node (ref "U6") (pin "1") (pinfunction "WE#_1") (pintype "unspecified"))
    )
    (net (code "93") (name "WE#5") (class "Default")
      (node (ref "U10") (pin "9") (pinfunction "Y6_9") (pintype "unspecified"))
      (node (ref "U7") (pin "1") (pinfunction "WE#_1") (pintype "unspecified"))
    )
    (net (code "94") (name "WE#6") (class "Default")
      (node (ref "U10") (pin "7") (pinfunction "Y7_7") (pintype "unspecified"))
      (node (ref "U8") (pin "1") (pinfunction "WE#_1") (pintype "unspecified"))
    )
    (net (code "95") (name "unconnected-(H2-Pad1)") (class "Default")
      (node (ref "H2") (pin "1") (pinfunction "1_1") (pintype "input+no_connect"))
    )
    (net (code "96") (name "unconnected-(H2-Pad2)") (class "Default")
      (node (ref "H2") (pin "2") (pinfunction "2_2") (pintype "input+no_connect"))
    )
    (net (code "97") (name "unconnected-(H2-Pad9)") (class "Default")
      (node (ref "H2") (pin "9") (pinfunction "9_9") (pintype "input+no_connect"))
    )
    (net (code "98") (name "unconnected-(H2-Pad10)") (class "Default")
      (node (ref "H2") (pin "10") (pinfunction "10_10") (pintype "input+no_connect"))
    )
    (net (code "99") (name "unconnected-(H9-Pad1)") (class "Default")
      (node (ref "H9") (pin "1") (pinfunction "1_1") (pintype "input+no_connect"))
    )
    (net (code "100") (name "unconnected-(H9-Pad2)") (class "Default")
      (node (ref "H9") (pin "2") (pinfunction "2_2") (pintype "input+no_connect"))
    )
    (net (code "101") (name "unconnected-(H9-Pad9)") (class "Default")
      (node (ref "H9") (pin "9") (pinfunction "9_9") (pintype "input+no_connect"))
    )
    (net (code "102") (name "unconnected-(H9-Pad10)") (class "Default")
      (node (ref "H9") (pin "10") (pinfunction "10_10") (pintype "input+no_connect"))
    )
    (net (code "103") (name "unconnected-(U10-Y0-Pad15)") (class "Default")
      (node (ref "U10") (pin "15") (pinfunction "Y0_15") (pintype "unspecified+no_connect"))
    )
    (net (code "104") (name "unconnected-(U11-Y0-Pad15)") (class "Default")
      (node (ref "U11") (pin "15") (pinfunction "Y0_15") (pintype "unspecified+no_connect"))
    )
    (net (code "105") (name "unconnected-(U12-Y0-Pad15)") (class "Default")
      (node (ref "U12") (pin "15") (pinfunction "Y0_15") (pintype "unspecified+no_connect"))
    )
    (net (code "106") (name "unconnected-(U13-N.C-Pad1)") (class "Default")
      (node (ref "U13") (pin "1") (pinfunction "N.C_1") (pintype "unspecified+no_connect"))
    )
    (net (code "107") (name "unconnected-(U14-N.C-Pad1)") (class "Default")
      (node (ref "U14") (pin "1") (pinfunction "N.C_1") (pintype "unspecified+no_connect"))
    )
    (net (code "108") (name "unconnected-(USB1-EH-Pad7)") (class "Default")
      (node (ref "USB1") (pin "7") (pinfunction "EH_7") (pintype "unspecified+no_connect"))
    )
  )
)
